# Titan_v1p1_180.net
KiCad netlist of a schematic drawn in EAGLE
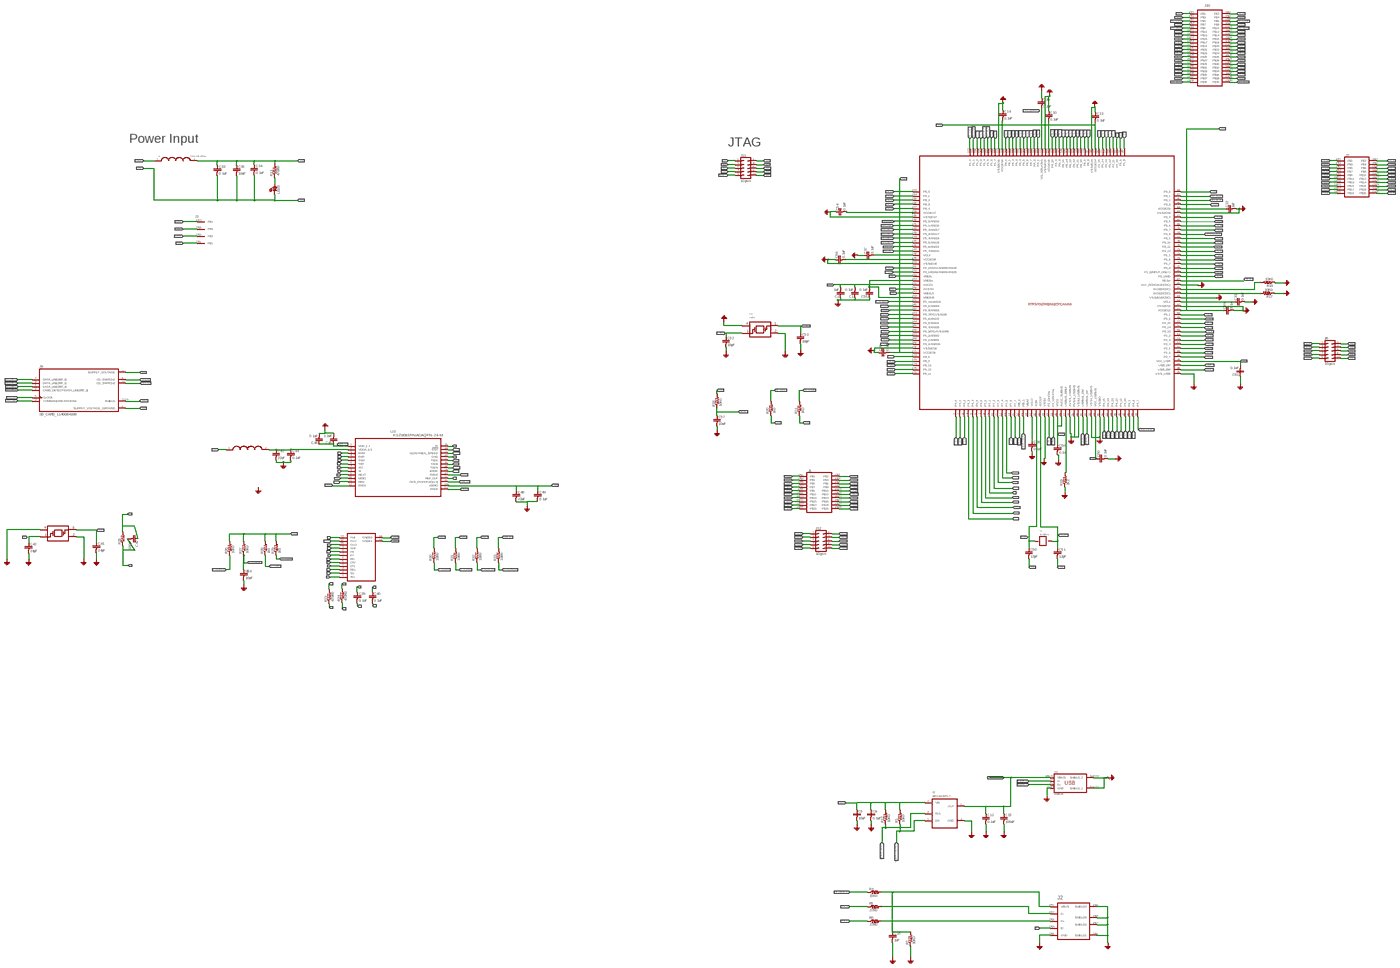
[diagram p0: schematic, sheet 1, overview]
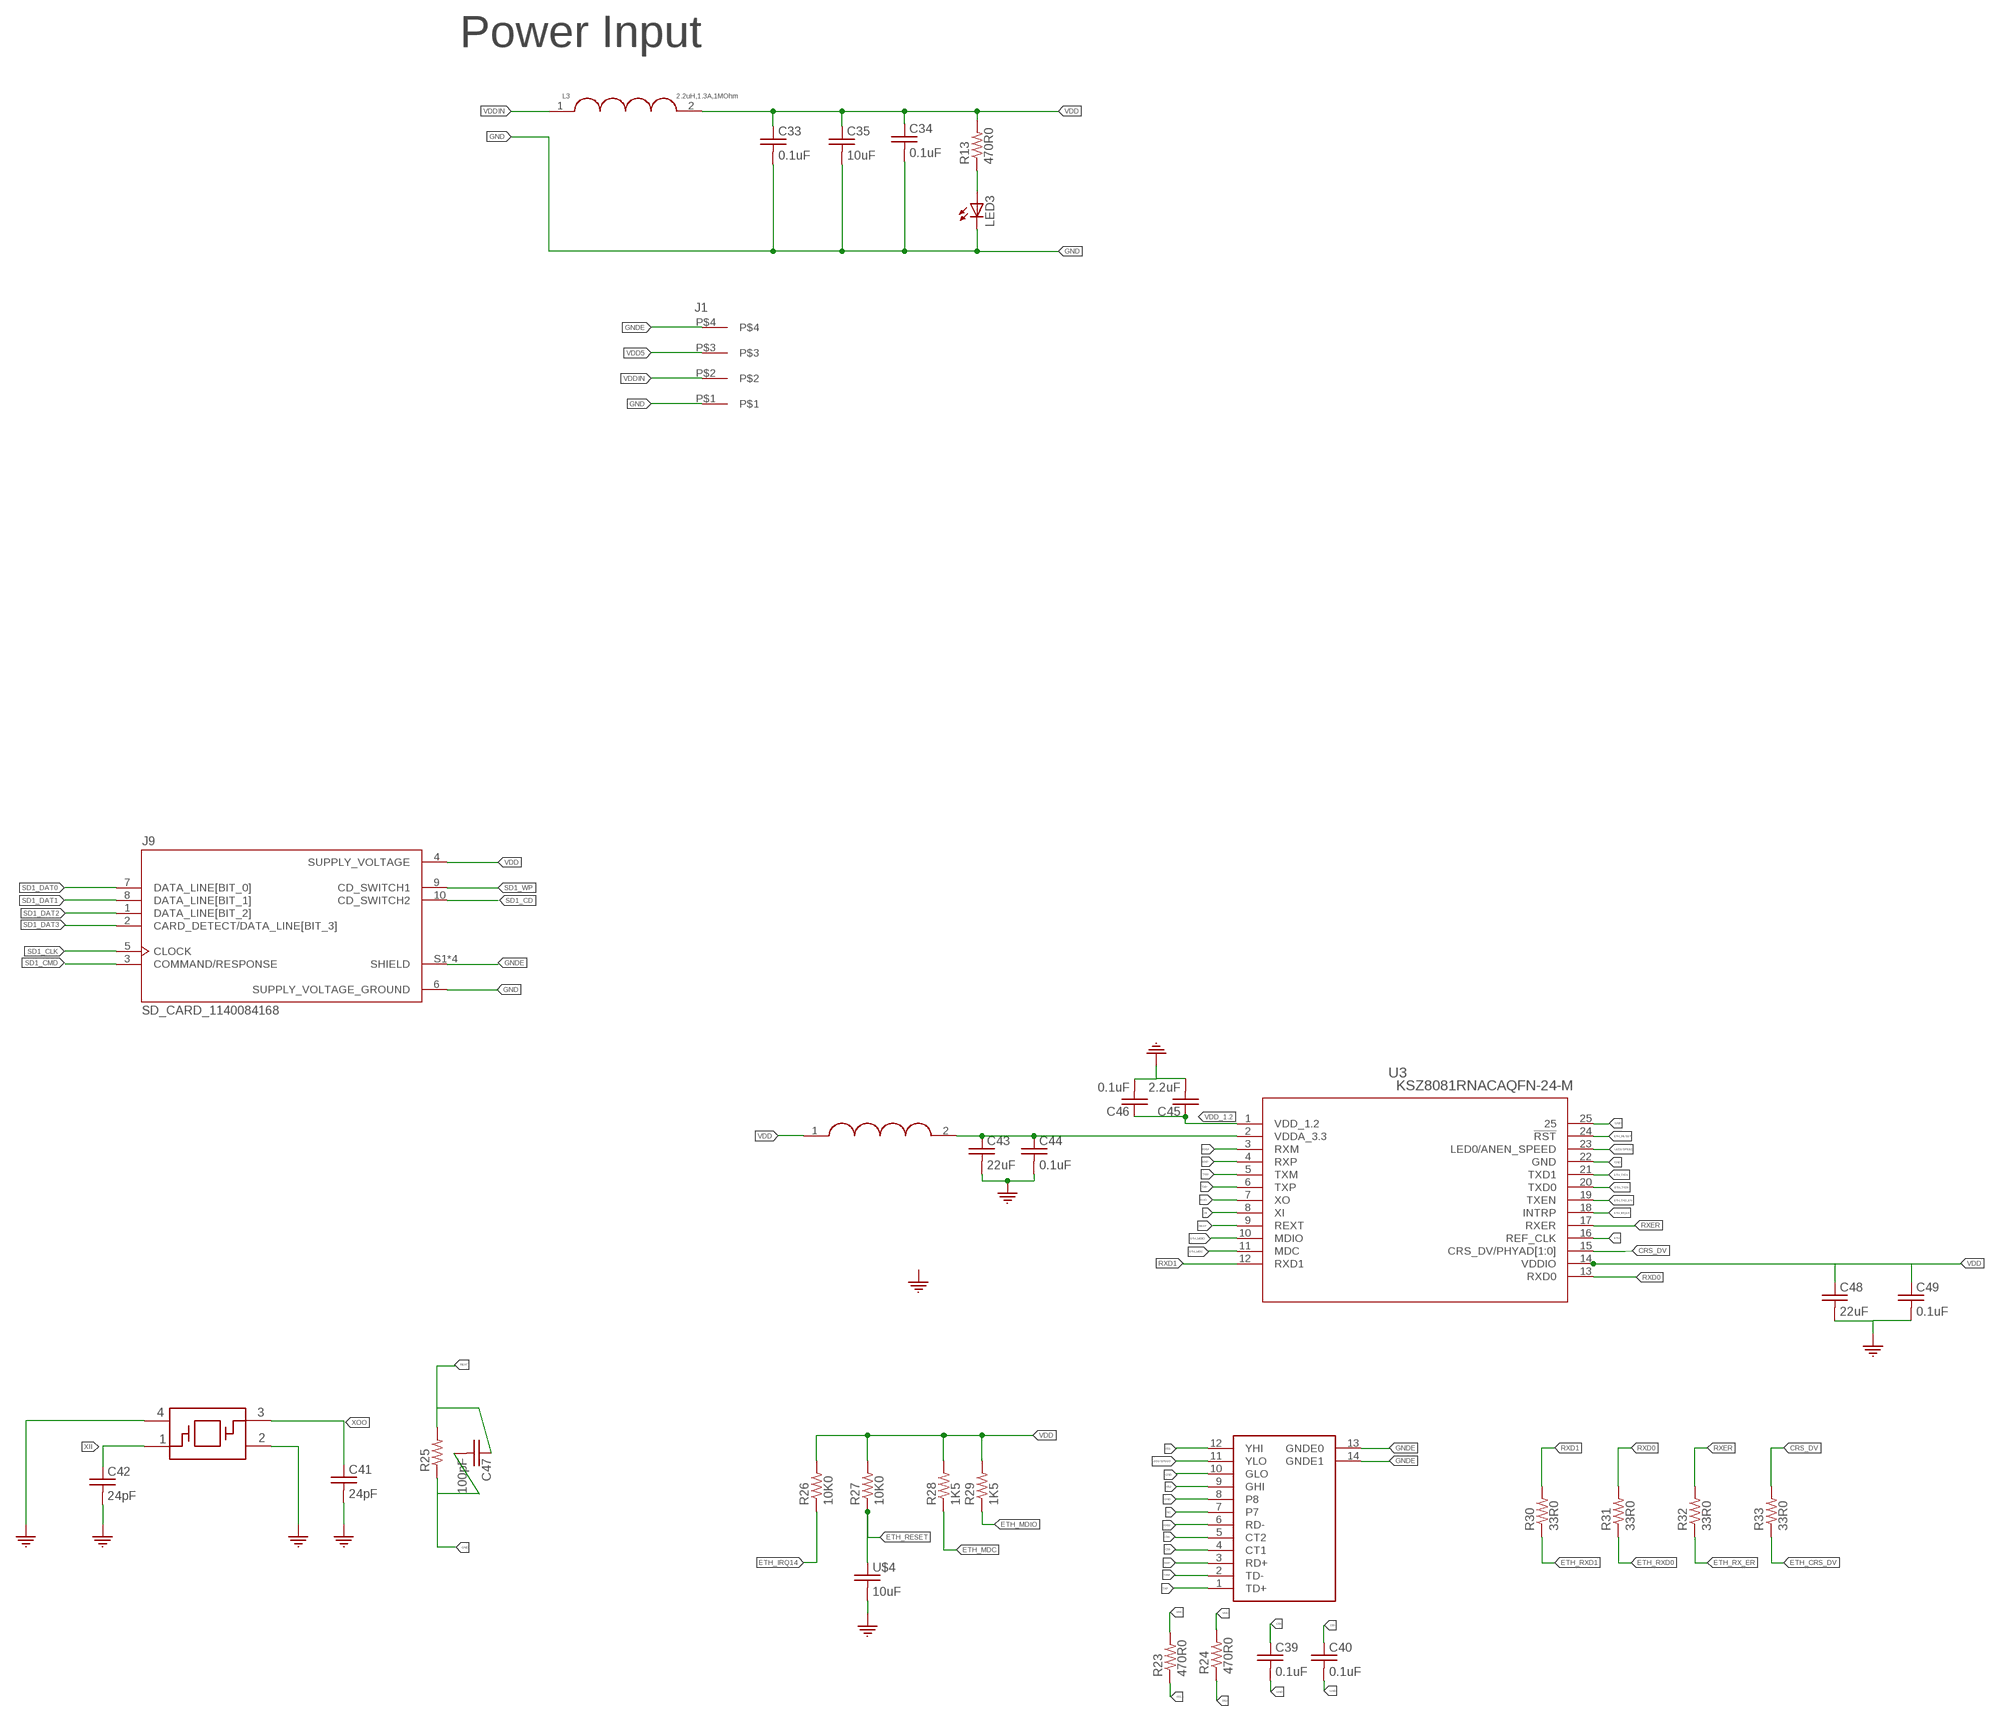
[diagram p1: schematic, sheet 1, part 1 of 4]
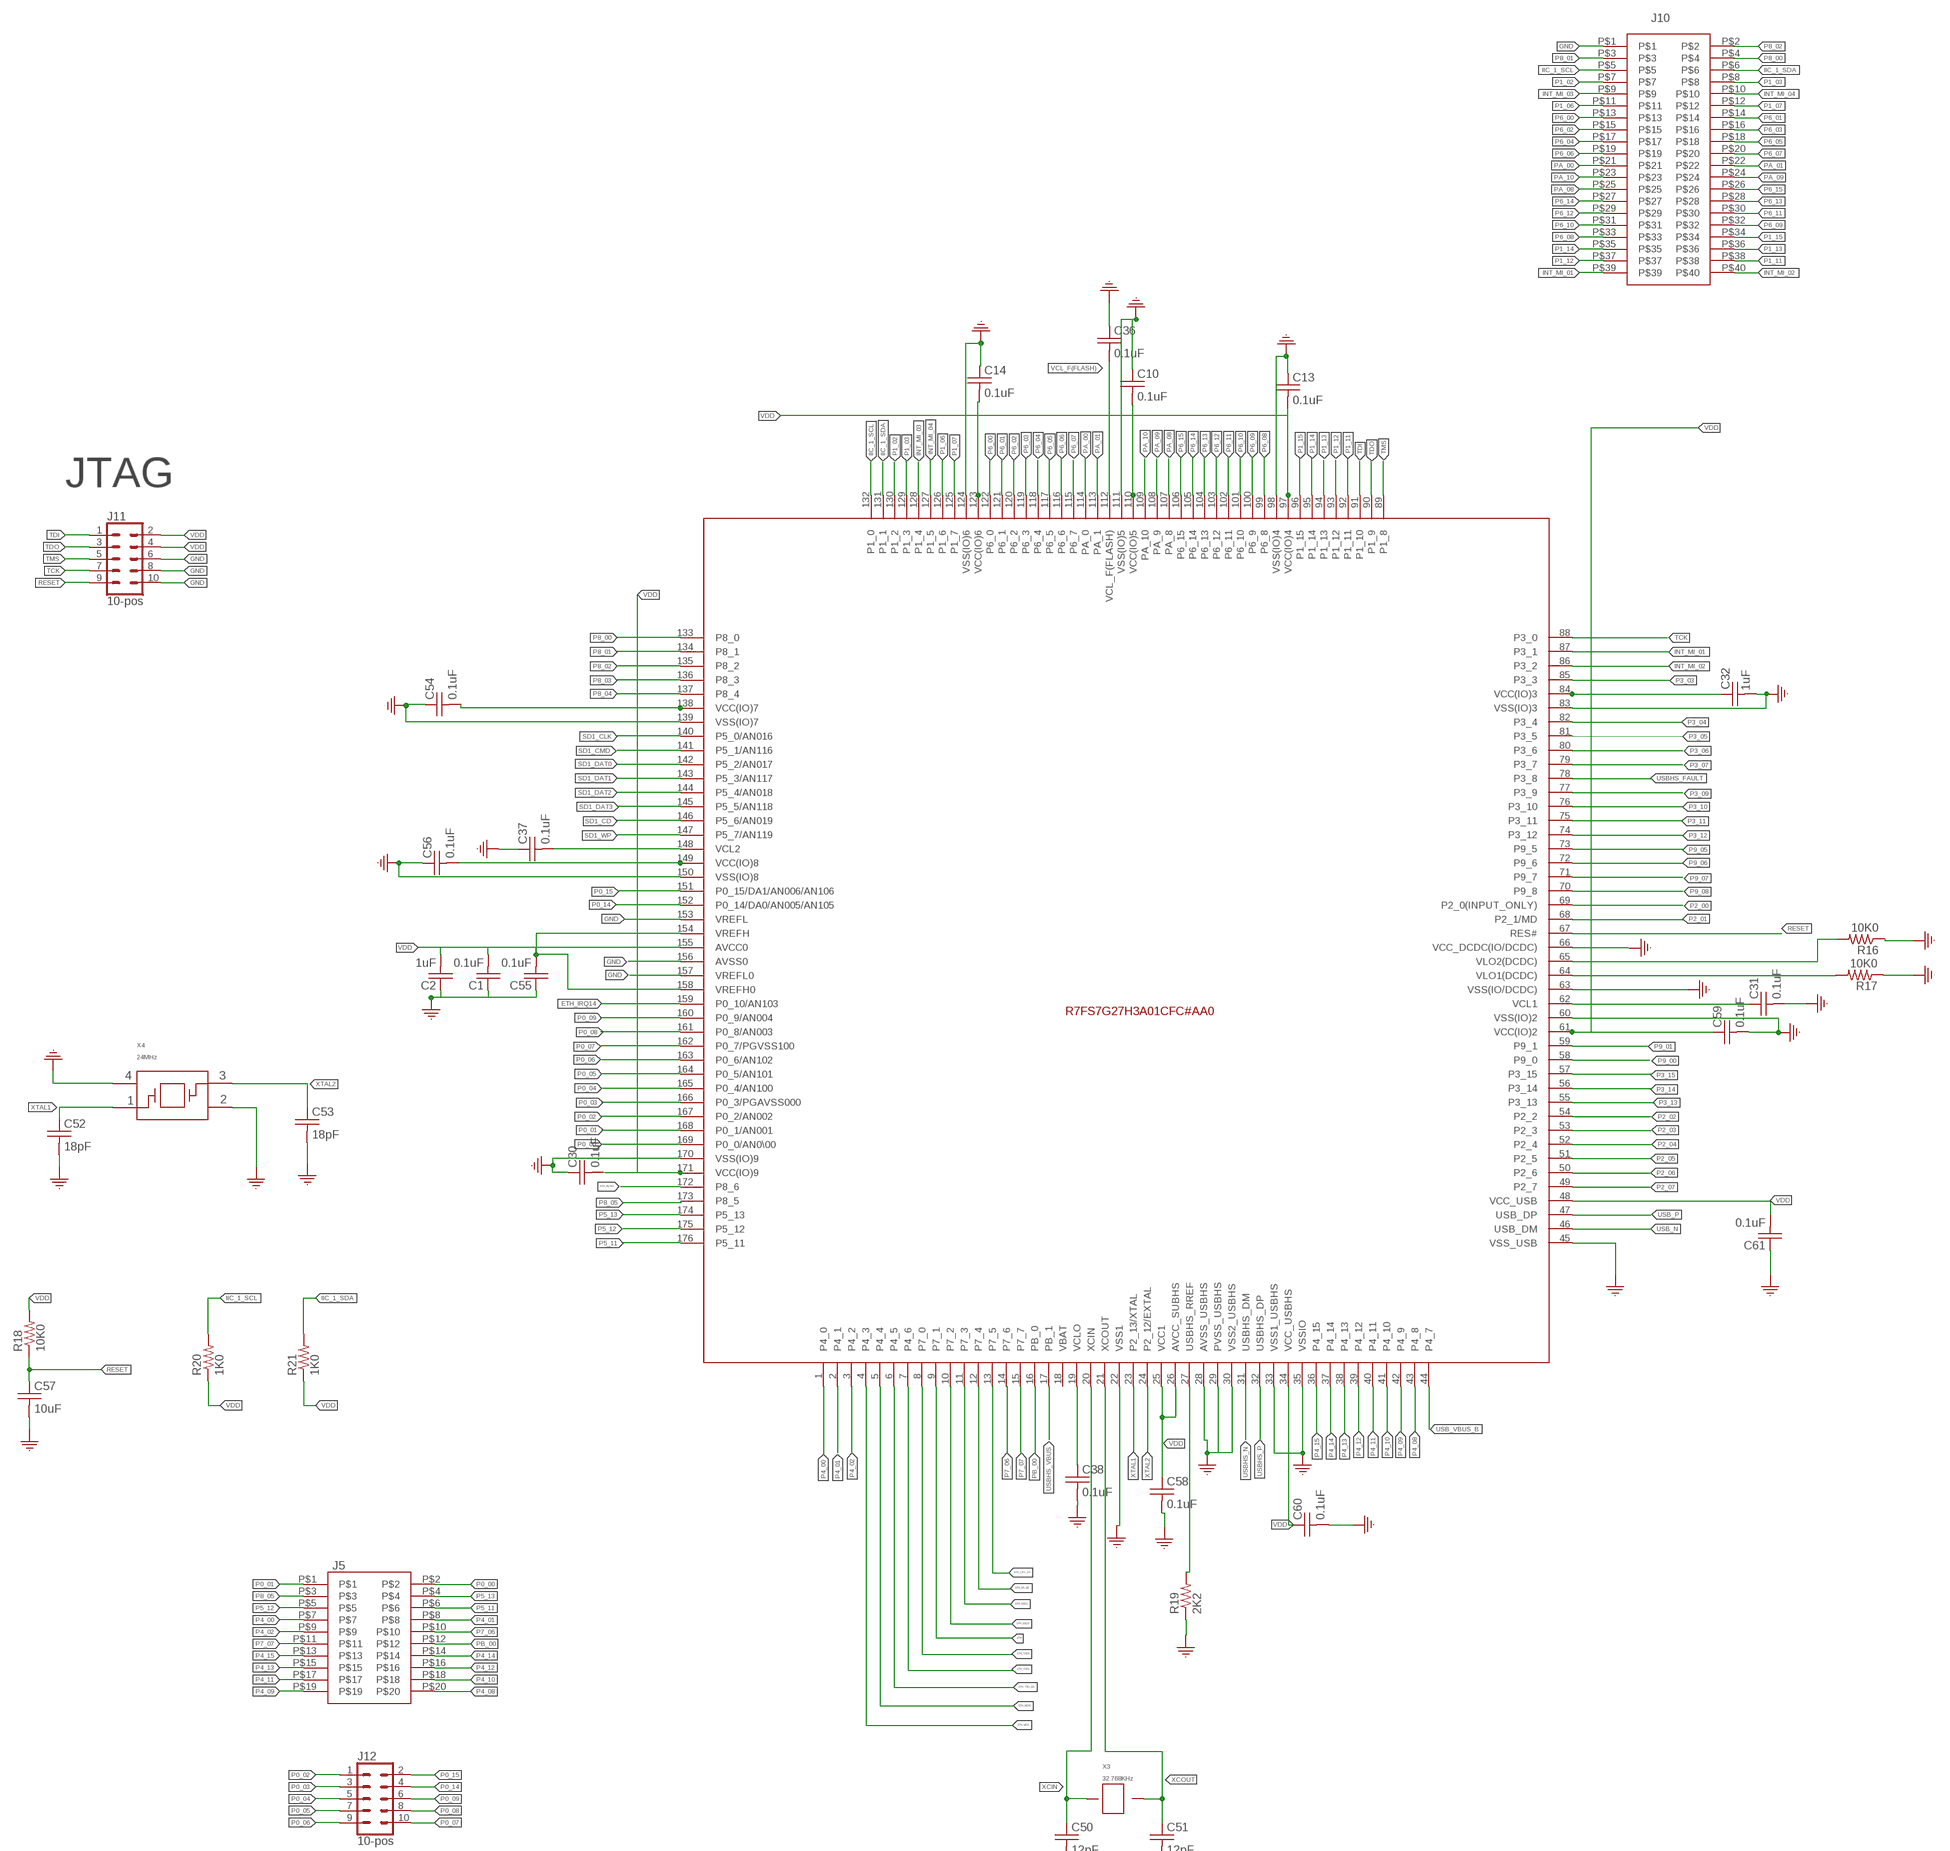
[diagram p2: schematic, sheet 1, part 2 of 4]
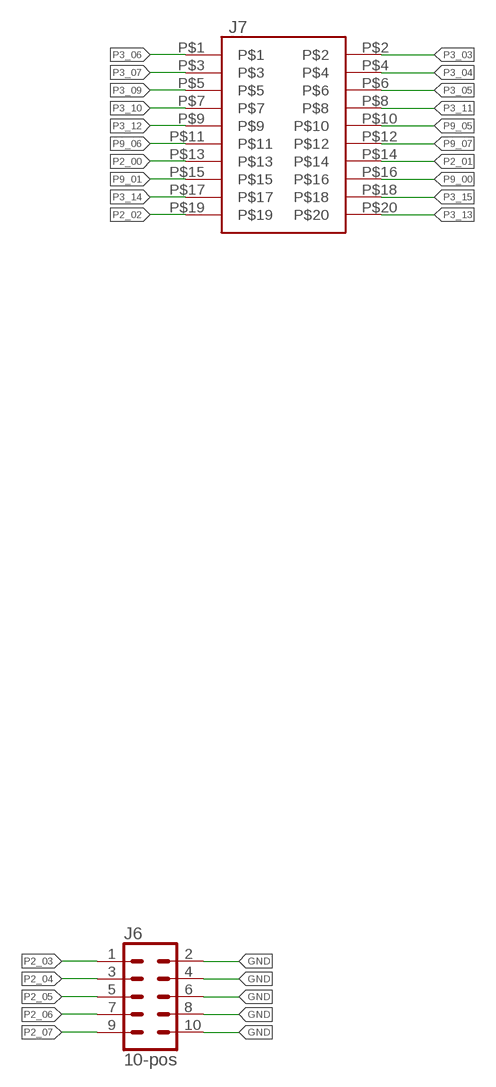
[diagram p3: schematic, sheet 1, part 3 of 4]
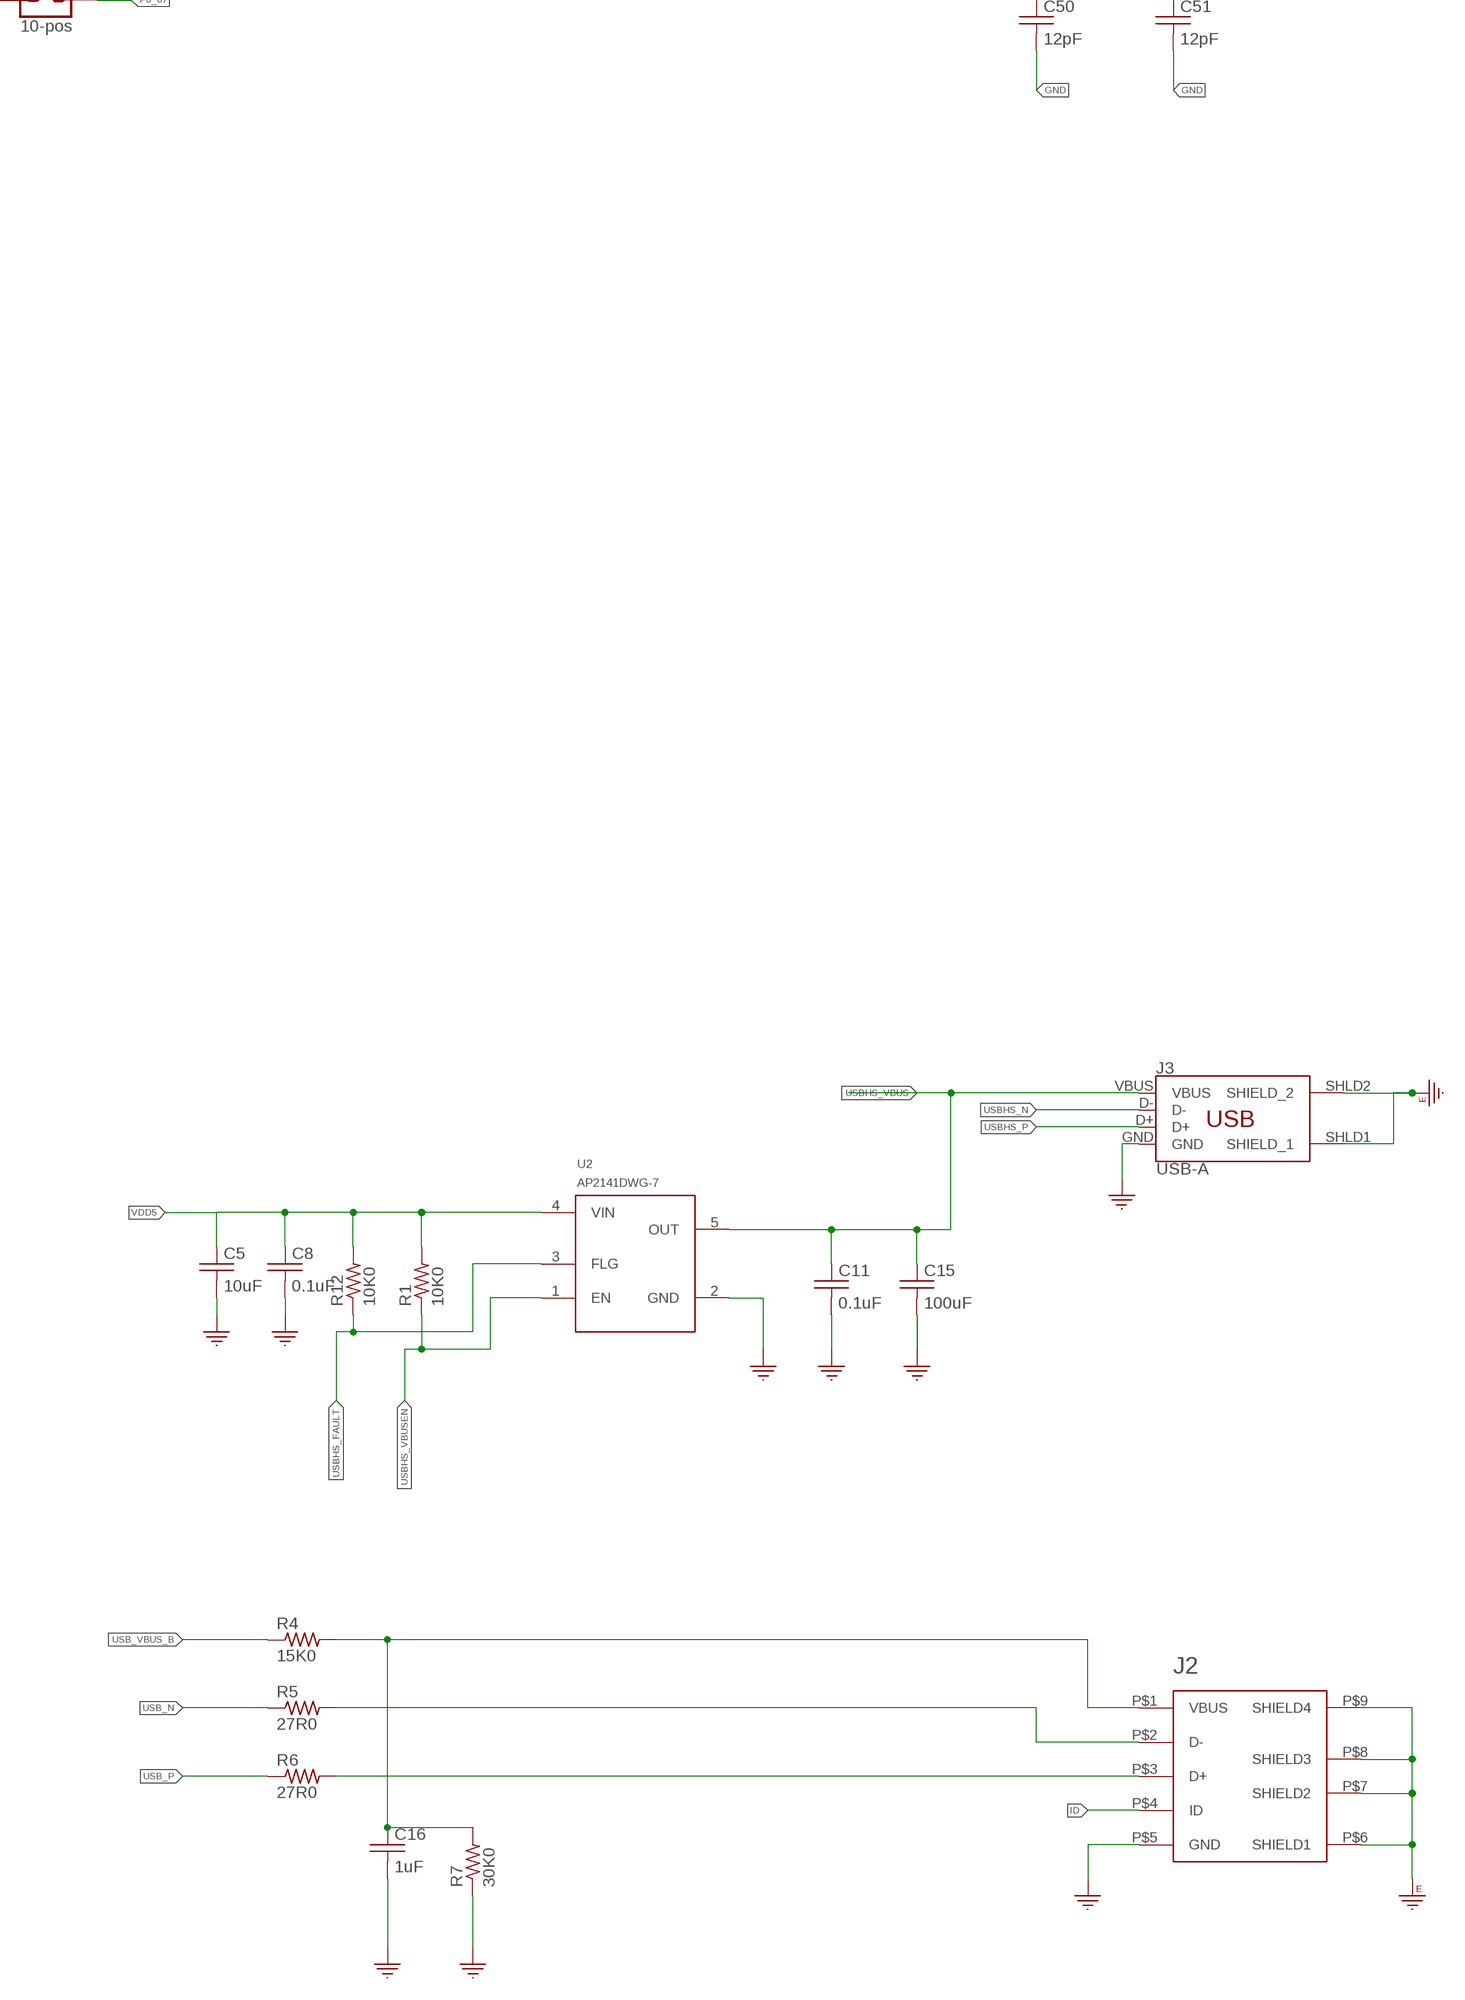
[diagram p4: schematic, sheet 1, part 4 of 4]

(export (version "E")
  (design (tool "Eeschema 10.0.6"))
  (components
    (comp (ref "C1")
      (value "0.1uF")
      (footprint "eagle-import:0402")
      (fields (field (name "PARTNO") "CL05F104ZO5NNNC"))
      (libsource (lib "eagle-import") (part "C_0402_0.1UF"))
    )
    (comp (ref "C2")
      (value "1uF")
      (footprint "eagle-import:0402")
      (fields (field (name "PARTNO") "CL05A105KO5NNNC"))
      (libsource (lib "eagle-import") (part "C_0402_1UF"))
    )
    (comp (ref "C5")
      (value "10uF")
      (footprint "eagle-import:0402")
      (fields (field (name "PARTNO") "CL05A106MP8NUB8"))
      (libsource (lib "eagle-import") (part "C_0402_10UF"))
    )
    (comp (ref "C8")
      (value "0.1uF")
      (footprint "eagle-import:0402")
      (fields (field (name "PARTNO") "CL05F104ZO5NNNC"))
      (libsource (lib "eagle-import") (part "C_0402_0.1UF"))
    )
    (comp (ref "C10")
      (value "0.1uF")
      (footprint "eagle-import:0402")
      (fields (field (name "PARTNO") "CL05F104ZO5NNNC"))
      (libsource (lib "eagle-import") (part "C_0402_0.1UF"))
    )
    (comp (ref "C11")
      (value "0.1uF")
      (footprint "eagle-import:0402")
      (fields (field (name "PARTNO") "CL05F104ZO5NNNC"))
      (libsource (lib "eagle-import") (part "C_0402_0.1UF"))
    )
    (comp (ref "C13")
      (value "0.1uF")
      (footprint "eagle-import:0402")
      (fields (field (name "PARTNO") "CL05F104ZO5NNNC"))
      (libsource (lib "eagle-import") (part "C_0402_0.1UF"))
    )
    (comp (ref "C14")
      (value "0.1uF")
      (footprint "eagle-import:0402")
      (fields (field (name "PARTNO") "CL05F104ZO5NNNC"))
      (libsource (lib "eagle-import") (part "C_0402_0.1UF"))
    )
    (comp (ref "C15")
      (value "100uF")
      (footprint "eagle-import:C1210")
      (fields (field (name "PARTNO") "TL8A0107M010D"))
      (libsource (lib "eagle-import") (part "C_1210"))
    )
    (comp (ref "C16")
      (value "1uF")
      (footprint "eagle-import:0402")
      (fields (field (name "PARTNO") "CL05A105KO5NNNC"))
      (libsource (lib "eagle-import") (part "C_0402_1UF"))
    )
    (comp (ref "C30")
      (value "0.1uF")
      (footprint "eagle-import:0402")
      (fields (field (name "PARTNO") "CL05F104ZO5NNNC"))
      (libsource (lib "eagle-import") (part "C_0402_0.1UF"))
    )
    (comp (ref "C31")
      (value "0.1uF")
      (footprint "eagle-import:0402")
      (fields (field (name "PARTNO") "CL05F104ZO5NNNC"))
      (libsource (lib "eagle-import") (part "C_0402_0.1UF"))
    )
    (comp (ref "C32")
      (value "1uF")
      (footprint "eagle-import:0402")
      (fields (field (name "PARTNO") "CL05A105KO5NNNC"))
      (libsource (lib "eagle-import") (part "C_0402_1UF"))
    )
    (comp (ref "C33")
      (value "0.1uF")
      (footprint "eagle-import:0402")
      (fields (field (name "PARTNO") "CL05F104ZO5NNNC"))
      (libsource (lib "eagle-import") (part "C_0402_0.1UF"))
    )
    (comp (ref "C34")
      (value "0.1uF")
      (footprint "eagle-import:0402")
      (fields (field (name "PARTNO") "CL05F104ZO5NNNC"))
      (libsource (lib "eagle-import") (part "C_0402_0.1UF"))
    )
    (comp (ref "C35")
      (value "10uF")
      (footprint "eagle-import:0402")
      (fields (field (name "PARTNO") "CL05A106MP8NUB8"))
      (libsource (lib "eagle-import") (part "C_0402_10UF"))
    )
    (comp (ref "C36")
      (value "0.1uF")
      (footprint "eagle-import:0402")
      (fields (field (name "PARTNO") "CL05F104ZO5NNNC"))
      (libsource (lib "eagle-import") (part "C_0402_0.1UF"))
    )
    (comp (ref "C37")
      (value "0.1uF")
      (footprint "eagle-import:0402")
      (fields (field (name "PARTNO") "CL05F104ZO5NNNC"))
      (libsource (lib "eagle-import") (part "C_0402_0.1UF"))
    )
    (comp (ref "C38")
      (value "0.1uF")
      (footprint "eagle-import:0402")
      (fields (field (name "PARTNO") "CL05F104ZO5NNNC"))
      (libsource (lib "eagle-import") (part "C_0402_0.1UF"))
    )
    (comp (ref "C39")
      (value "0.1uF")
      (footprint "eagle-import:0402")
      (fields (field (name "PARTNO") "CL05F104ZO5NNNC"))
      (libsource (lib "eagle-import") (part "C_0402_0.1UF"))
    )
    (comp (ref "C40")
      (value "0.1uF")
      (footprint "eagle-import:0402")
      (fields (field (name "PARTNO") "CL05F104ZO5NNNC"))
      (libsource (lib "eagle-import") (part "C_0402_0.1UF"))
    )
    (comp (ref "C41")
      (value "24pF")
      (footprint "eagle-import:0402")
      (fields (field (name "PARTNO") "CC0402GRNPO9BN240"))
      (libsource (lib "eagle-import") (part "C_0402_24PF"))
    )
    (comp (ref "C42")
      (value "24pF")
      (footprint "eagle-import:0402")
      (fields (field (name "PARTNO") "CC0402GRNPO9BN240"))
      (libsource (lib "eagle-import") (part "C_0402_24PF"))
    )
    (comp (ref "C43")
      (value "22uF")
      (footprint "eagle-import:0402")
      (fields (field (name "PARTNO") "CL05A226MQ5N6J8"))
      (libsource (lib "eagle-import") (part "C_0402_22UF"))
    )
    (comp (ref "C44")
      (value "0.1uF")
      (footprint "eagle-import:0402")
      (fields (field (name "PARTNO") "CL05F104ZO5NNNC"))
      (libsource (lib "eagle-import") (part "C_0402_0.1UF"))
    )
    (comp (ref "C45")
      (value "2.2uF")
      (footprint "eagle-import:0402")
      (fields (field (name "PARTNO") "GRM155C81C225ME15D"))
      (libsource (lib "eagle-import") (part "C_0402_2.2UF"))
    )
    (comp (ref "C46")
      (value "0.1uF")
      (footprint "eagle-import:0402")
      (fields (field (name "PARTNO") "CL05F104ZO5NNNC"))
      (libsource (lib "eagle-import") (part "C_0402_0.1UF"))
    )
    (comp (ref "C47")
      (value "100pF")
      (footprint "eagle-import:0402")
      (fields (field (name "PARTNO") "CL05C101JB5NNNC"))
      (libsource (lib "eagle-import") (part "C_0402_100PF"))
    )
    (comp (ref "C48")
      (value "22uF")
      (footprint "eagle-import:0402")
      (fields (field (name "PARTNO") "CL05A226MQ5N6J8"))
      (libsource (lib "eagle-import") (part "C_0402_22UF"))
    )
    (comp (ref "C49")
      (value "0.1uF")
      (footprint "eagle-import:0402")
      (fields (field (name "PARTNO") "CL05F104ZO5NNNC"))
      (libsource (lib "eagle-import") (part "C_0402_0.1UF"))
    )
    (comp (ref "C50")
      (value "12pF")
      (footprint "eagle-import:0402")
      (fields (field (name "PARTNO") "CL05C120JB5NNNC"))
      (libsource (lib "eagle-import") (part "C_0402_12PF"))
    )
    (comp (ref "C51")
      (value "12pF")
      (footprint "eagle-import:0402")
      (fields (field (name "PARTNO") "CL05C120JB5NNNC"))
      (libsource (lib "eagle-import") (part "C_0402_12PF"))
    )
    (comp (ref "C52")
      (value "18pF")
      (footprint "eagle-import:0402")
      (fields (field (name "PARTNO") "UMK105CG180JV-F"))
      (libsource (lib "eagle-import") (part "C_0402_18PF"))
    )
    (comp (ref "C53")
      (value "18pF")
      (footprint "eagle-import:0402")
      (fields (field (name "PARTNO") "UMK105CG180JV-F"))
      (libsource (lib "eagle-import") (part "C_0402_18PF"))
    )
    (comp (ref "C54")
      (value "0.1uF")
      (footprint "eagle-import:0402")
      (fields (field (name "PARTNO") "CL05F104ZO5NNNC"))
      (libsource (lib "eagle-import") (part "C_0402_0.1UF"))
    )
    (comp (ref "C55")
      (value "0.1uF")
      (footprint "eagle-import:0402")
      (fields (field (name "PARTNO") "CL05F104ZO5NNNC"))
      (libsource (lib "eagle-import") (part "C_0402_0.1UF"))
    )
    (comp (ref "C56")
      (value "0.1uF")
      (footprint "eagle-import:0402")
      (fields (field (name "PARTNO") "CL05F104ZO5NNNC"))
      (libsource (lib "eagle-import") (part "C_0402_0.1UF"))
    )
    (comp (ref "C57")
      (value "10uF")
      (footprint "eagle-import:0402")
      (fields (field (name "PARTNO") "CL05A106MP8NUB8"))
      (libsource (lib "eagle-import") (part "C_0402_10UF"))
    )
    (comp (ref "C58")
      (value "0.1uF")
      (footprint "eagle-import:0402")
      (fields (field (name "PARTNO") "CL05F104ZO5NNNC"))
      (libsource (lib "eagle-import") (part "C_0402_0.1UF"))
    )
    (comp (ref "C59")
      (value "0.1uF")
      (footprint "eagle-import:0402")
      (fields (field (name "PARTNO") "CL05F104ZO5NNNC"))
      (libsource (lib "eagle-import") (part "C_0402_0.1UF"))
    )
    (comp (ref "C60")
      (value "0.1uF")
      (footprint "eagle-import:0402")
      (fields (field (name "PARTNO") "CL05F104ZO5NNNC"))
      (libsource (lib "eagle-import") (part "C_0402_0.1UF"))
    )
    (comp (ref "C61")
      (value "0.1uF")
      (footprint "eagle-import:0402")
      (fields (field (name "PARTNO") "CL05F104ZO5NNNC"))
      (libsource (lib "eagle-import") (part "C_0402_0.1UF"))
    )
    (comp (ref "FB2/2")
      (value "120Ohm")
      (footprint "eagle-import:0603")
      (fields (field (name "PARTNO") "BLM18PG121SN1D"))
      (libsource (lib "eagle-import") (part "FB_0603_120_OHM0603"))
    )
    (comp (ref "J1")
      (value "4-pos")
      (footprint "eagle-import:1X4_3.81MM_PITCH")
      (fields (field (name "PARTNO") "691322310004"))
      (libsource (lib "eagle-import") (part "3.81MM_1_X_4_RT_ANGLE_PLUG_HEADER"))
    )
    (comp (ref "J2")
      (value "USB-B-Micro")
      (footprint "eagle-import:USB_MICRO-B")
      (fields (field (name "PARTNO") "10118192-0002LF"))
      (libsource (lib "eagle-import") (part "USB_MICRO-B"))
    )
    (comp (ref "J3")
      (value "USB-A")
      (footprint "eagle-import:USB_A_SMT")
      (fields (field (name "PARTNO") "87583-3010RPALF"))
      (libsource (lib "eagle-import") (part "USB_A"))
    )
    (comp (ref "J4")
      (value "RJ45")
      (footprint "eagle-import:RJ45_TH_ELEC")
      (fields (field (name "PARTNO") "13F-64GYD2PL2NL"))
      (libsource (lib "eagle-import") (part "RJ45_WITH_ELEC"))
    )
    (comp (ref "J5")
      (value "20-pos")
      (footprint "eagle-import:2_X_10_.1_INCH")
      (fields (field (name "PARTNO") "67996-420HLF"))
      (libsource (lib "eagle-import") (part "2_X_10_HEADER_GENERIC"))
    )
    (comp (ref "J6")
      (value "10-pos")
      (footprint "eagle-import:2X5")
      (fields (field (name "PARTNO") "PH2RA-10-UA"))
      (libsource (lib "eagle-import") (part "CONN_05X2_RAPTH"))
    )
    (comp (ref "J7")
      (value "20-pos")
      (footprint "eagle-import:2_X_10_.1_INCH")
      (fields (field (name "PARTNO") "67996-420HLF"))
      (libsource (lib "eagle-import") (part "2_X_10_HEADER_GENERIC"))
    )
    (comp (ref "J9")
      (value "SD_CARD_1140084168")
      (footprint "eagle-import:SD_CARD")
      (fields (field (name "MF") "Amphenol ICC") (field (name "PARTNO") "114-00841-68"))
      (libsource (lib "eagle-import") (part "SD_CARD_1140084168"))
    )
    (comp (ref "J10")
      (value "40-pos")
      (footprint "eagle-import:HEADER_2_X_20_.1_INCH")
      (fields (field (name "PARTNO") "61304021021"))
      (libsource (lib "eagle-import") (part "HEADER_2_X_20_GENERIC"))
    )
    (comp (ref "J11")
      (value "10-pos")
      (footprint "eagle-import:2X5")
      (fields (field (name "PARTNO") "PH2RA-10-UA"))
      (libsource (lib "eagle-import") (part "CONN_05X2_RAPTH"))
    )
    (comp (ref "J12")
      (value "10-pos")
      (footprint "eagle-import:2X5")
      (fields (field (name "PARTNO") "PH2RA-10-UA"))
      (libsource (lib "eagle-import") (part "CONN_05X2_RAPTH"))
    )
    (comp (ref "L3")
      (value "2.2uH,1.3A,1MOhm")
      (footprint "eagle-import:1008")
      (fields (field (name "PARTNO") "LQM2HPN2R2MG0L"))
      (libsource (lib "eagle-import") (part "INDUCTOR_1008_2.2_MH_1.3A"))
    )
    (comp (ref "LED3")
      (value "Green")
      (footprint "eagle-import:0805")
      (fields (field (name "PARTNO") "LG R971-KN-1"))
      (libsource (lib "eagle-import") (part "LED_0805_GREEN"))
    )
    (comp (ref "R1")
      (value "10K0")
      (footprint "eagle-import:0402")
      (fields (field (name "PARTNO") "RMCF0402JT10K0"))
      (libsource (lib "eagle-import") (part "R_0402_10K0"))
    )
    (comp (ref "R4")
      (value "15K0")
      (footprint "eagle-import:0402")
      (fields (field (name "PARTNO") "RMCF0402JT15K0"))
      (libsource (lib "eagle-import") (part "R_0402_15K0"))
    )
    (comp (ref "R5")
      (value "27R0")
      (footprint "eagle-import:0402")
      (fields (field (name "PARTNO") "RMCF0402JT27R0"))
      (libsource (lib "eagle-import") (part "R_0402_27R0"))
    )
    (comp (ref "R6")
      (value "27R0")
      (footprint "eagle-import:0402")
      (fields (field (name "PARTNO") "RMCF0402JT27R0"))
      (libsource (lib "eagle-import") (part "R_0402_27R0"))
    )
    (comp (ref "R7")
      (value "30K0")
      (footprint "eagle-import:0402")
      (fields (field (name "PARTNO") "RC0402JR-0730KL"))
      (libsource (lib "eagle-import") (part "R_0402_30K0"))
    )
    (comp (ref "R12")
      (value "10K0")
      (footprint "eagle-import:0402")
      (fields (field (name "PARTNO") "RMCF0402JT10K0"))
      (libsource (lib "eagle-import") (part "R_0402_10K0"))
    )
    (comp (ref "R13")
      (value "470R0")
      (footprint "eagle-import:0402")
      (fields (field (name "PARTNO") "RMCF0402JT470R"))
      (libsource (lib "eagle-import") (part "R_0402_470R0"))
    )
    (comp (ref "R16")
      (value "10K0")
      (footprint "eagle-import:0402")
      (fields (field (name "PARTNO") "RMCF0402JT10K0"))
      (libsource (lib "eagle-import") (part "R_0402_10K0"))
    )
    (comp (ref "R17")
      (value "10K0")
      (footprint "eagle-import:0402")
      (fields (field (name "PARTNO") "RMCF0402JT10K0"))
      (libsource (lib "eagle-import") (part "R_0402_10K0"))
    )
    (comp (ref "R18")
      (value "10K0")
      (footprint "eagle-import:0402")
      (fields (field (name "PARTNO") "RMCF0402JT10K0"))
      (libsource (lib "eagle-import") (part "R_0402_10K0"))
    )
    (comp (ref "R19")
      (value "2K2")
      (footprint "eagle-import:0402")
      (fields (field (name "PARTNO") "RMCF0402JT2K20"))
      (libsource (lib "eagle-import") (part "R_0402_2K2"))
    )
    (comp (ref "R20")
      (value "1K0")
      (footprint "eagle-import:0402")
      (fields (field (name "PARTNO") "CRG0402J1K0"))
      (libsource (lib "eagle-import") (part "R_0402_1K0"))
    )
    (comp (ref "R21")
      (value "1K0")
      (footprint "eagle-import:0402")
      (fields (field (name "PARTNO") "CRG0402J1K0"))
      (libsource (lib "eagle-import") (part "R_0402_1K0"))
    )
    (comp (ref "R23")
      (value "470R0")
      (footprint "eagle-import:0402")
      (fields (field (name "PARTNO") "RMCF0402JT470R"))
      (libsource (lib "eagle-import") (part "R_0402_470R0"))
    )
    (comp (ref "R24")
      (value "470R0")
      (footprint "eagle-import:0402")
      (fields (field (name "PARTNO") "RMCF0402JT470R"))
      (libsource (lib "eagle-import") (part "R_0402_470R0"))
    )
    (comp (ref "R25")
      (value "6K49")
      (footprint "eagle-import:0402")
      (fields (field (name "PARTNO") "RMCF0402FT6K49"))
      (libsource (lib "eagle-import") (part "R_0402_6K49"))
    )
    (comp (ref "R26")
      (value "10K0")
      (footprint "eagle-import:0402")
      (fields (field (name "PARTNO") "RMCF0402JT10K0"))
      (libsource (lib "eagle-import") (part "R_0402_10K0"))
    )
    (comp (ref "R27")
      (value "10K0")
      (footprint "eagle-import:0402")
      (fields (field (name "PARTNO") "RMCF0402JT10K0"))
      (libsource (lib "eagle-import") (part "R_0402_10K0"))
    )
    (comp (ref "R28")
      (value "1K5")
      (footprint "eagle-import:0402")
      (fields (field (name "PARTNO") "RMCF0402JT1K50"))
      (libsource (lib "eagle-import") (part "R_0402_1K5"))
    )
    (comp (ref "R29")
      (value "1K5")
      (footprint "eagle-import:0402")
      (fields (field (name "PARTNO") "RMCF0402JT1K50"))
      (libsource (lib "eagle-import") (part "R_0402_1K5"))
    )
    (comp (ref "R30")
      (value "33R0")
      (footprint "eagle-import:0402")
      (fields (field (name "PARTNO") "RMCF0402JT33R0"))
      (libsource (lib "eagle-import") (part "R_0402_33R0"))
    )
    (comp (ref "R31")
      (value "33R0")
      (footprint "eagle-import:0402")
      (fields (field (name "PARTNO") "RMCF0402JT33R0"))
      (libsource (lib "eagle-import") (part "R_0402_33R0"))
    )
    (comp (ref "R32")
      (value "33R0")
      (footprint "eagle-import:0402")
      (fields (field (name "PARTNO") "RMCF0402JT33R0"))
      (libsource (lib "eagle-import") (part "R_0402_33R0"))
    )
    (comp (ref "R33")
      (value "33R0")
      (footprint "eagle-import:0402")
      (fields (field (name "PARTNO") "RMCF0402JT33R0"))
      (libsource (lib "eagle-import") (part "R_0402_33R0"))
    )
    (comp (ref "U$4")
      (value "10uF")
      (footprint "eagle-import:0402")
      (fields (field (name "PARTNO") "CL05A106MP8NUB8"))
      (libsource (lib "eagle-import") (part "C_0402_10UF"))
    )
    (comp (ref "U2")
      (value "AP2151DWG-7")
      (footprint "eagle-import:SOT-23-5")
      (fields (field (name "PARTNO") "AP2151WG-7"))
      (libsource (lib "eagle-import") (part "AP2151DWG-7"))
    )
    (comp (ref "U3")
      (value "KSZ8081RNACAQFN-24-M")
      (footprint "eagle-import:QFN-24-M")
      (fields (field (name "PARTNO") "KSZ8081RNACA"))
      (libsource (lib "eagle-import") (part "KSZ8081RNACAQFN-24-M"))
    )
    (comp (ref "U4")
      (value "S7G2LQFP176")
      (footprint "eagle-import:LQFP176_24X24")
      (fields (field (name "PARTNO") "R7FS7G27H3A01CFC#AA0"))
      (libsource (lib "eagle-import") (part "S7G2_X_176"))
    )
    (comp (ref "U5")
      (value "25MHz")
      (footprint "eagle-import:SMD_3225")
      (fields (field (name "PARTNO") "FA-238 25.0000MB-B3"))
      (libsource (lib "eagle-import") (part "XTAL_25_MHZ"))
    )
    (comp (ref "X3")
      (value "32.768KHz")
      (footprint "eagle-import:SMD_X_2_PADS")
      (fields (field (name "PARTNO") "ABS07-32.768KHZ-T"))
      (libsource (lib "eagle-import") (part "XTAL_32.768KHZ"))
    )
    (comp (ref "X4")
      (value "24MHz")
      (footprint "eagle-import:SMD_3225")
      (fields (field (name "PARTNO") "FA-238 24.0000MB-C3 "))
      (libsource (lib "eagle-import") (part "XTAL_24_MHZ"))
    )
  )
  (nets
    (net (code "1") (name "C58") (class "Default")
      (node (ref "C39") (pin "P$1") (pinfunction "1_P$1") (pintype "passive"))
      (node (ref "J4") (pin "4") (pinfunction "CT1_4") (pintype "bidirectional"))
    )
    (net (code "2") (name "C60") (class "Default")
      (node (ref "C40") (pin "P$1") (pinfunction "1_P$1") (pintype "passive"))
      (node (ref "J4") (pin "5") (pinfunction "CT2_5") (pintype "bidirectional"))
    )
    (net (code "3") (name "CRS_DV") (class "Default")
      (node (ref "R33") (pin "P$2") (pinfunction "2_P$2") (pintype "passive"))
      (node (ref "U3") (pin "15") (pinfunction "CRS_DV/PHYAD[1:0]_15") (pintype "bidirectional"))
    )
    (net (code "4") (name "ETH") (class "Default")
      (node (ref "U3") (pin "16") (pinfunction "REF_CLK_16") (pintype "bidirectional"))
      (node (ref "U4") (pin "9") (pinfunction "P7_1_9") (pintype "bidirectional"))
    )
    (net (code "5") (name "ETH_CRS_DV") (class "Default")
      (node (ref "R33") (pin "P$1") (pinfunction "1_P$1") (pintype "passive"))
      (node (ref "U4") (pin "13") (pinfunction "P7_5_13") (pintype "bidirectional"))
    )
    (net (code "6") (name "ETH_IRQ14") (class "Default")
      (node (ref "R26") (pin "P$1") (pinfunction "1_P$1") (pintype "passive"))
      (node (ref "U3") (pin "18") (pinfunction "INTRP_18") (pintype "bidirectional"))
      (node (ref "U4") (pin "159") (pinfunction "P0_10/AN103_159") (pintype "bidirectional"))
    )
    (net (code "7") (name "ETH_MDC") (class "Default")
      (node (ref "R28") (pin "P$1") (pinfunction "1_P$1") (pintype "passive"))
      (node (ref "U3") (pin "11") (pinfunction "MDC_11") (pintype "input"))
      (node (ref "U4") (pin "4") (pinfunction "P4_3_4") (pintype "bidirectional"))
    )
    (net (code "8") (name "ETH_MDIO") (class "Default")
      (node (ref "R29") (pin "P$1") (pinfunction "1_P$1") (pintype "passive"))
      (node (ref "U3") (pin "10") (pinfunction "MDIO_10") (pintype "bidirectional"))
      (node (ref "U4") (pin "5") (pinfunction "P4_4_5") (pintype "bidirectional"))
    )
    (net (code "9") (name "ETH_RESET") (class "Default")
      (node (ref "R27") (pin "P$1") (pinfunction "1_P$1") (pintype "passive"))
      (node (ref "U$4") (pin "P$1") (pinfunction "1_P$1") (pintype "passive"))
      (node (ref "U3") (pin "24") (pinfunction "~{RST}_24") (pintype "input"))
      (node (ref "U4") (pin "172") (pinfunction "P8_6_172") (pintype "bidirectional"))
    )
    (net (code "10") (name "ETH_RXD0") (class "Default")
      (node (ref "R31") (pin "P$1") (pinfunction "1_P$1") (pintype "passive"))
      (node (ref "U4") (pin "10") (pinfunction "P7_2_10") (pintype "bidirectional"))
    )
    (net (code "11") (name "ETH_RXD1") (class "Default")
      (node (ref "R30") (pin "P$1") (pinfunction "1_P$1") (pintype "passive"))
      (node (ref "U4") (pin "11") (pinfunction "P7_3_11") (pintype "bidirectional"))
    )
    (net (code "12") (name "ETH_RX_ER") (class "Default")
      (node (ref "R32") (pin "P$1") (pinfunction "1_P$1") (pintype "passive"))
      (node (ref "U4") (pin "12") (pinfunction "P7_4_12") (pintype "bidirectional"))
    )
    (net (code "13") (name "ETH_TXD0") (class "Default")
      (node (ref "U3") (pin "20") (pinfunction "TXD0_20") (pintype "input"))
      (node (ref "U4") (pin "8") (pinfunction "P7_0_8") (pintype "bidirectional"))
    )
    (net (code "14") (name "ETH_TXD1") (class "Default")
      (node (ref "U3") (pin "21") (pinfunction "TXD1_21") (pintype "bidirectional"))
      (node (ref "U4") (pin "7") (pinfunction "P4_6_7") (pintype "bidirectional"))
    )
    (net (code "15") (name "ETH_TXD_EN") (class "Default")
      (node (ref "U3") (pin "19") (pinfunction "TXEN_19") (pintype "input"))
      (node (ref "U4") (pin "6") (pinfunction "P4_5_6") (pintype "bidirectional"))
    )
    (net (code "16") (name "GND") (class "Default")
      (node (ref "C1") (pin "P$1") (pinfunction "1_P$1") (pintype "passive"))
      (node (ref "C10") (pin "P$1") (pinfunction "1_P$1") (pintype "passive"))
      (node (ref "C11") (pin "P$2") (pinfunction "2_P$2") (pintype "passive"))
      (node (ref "C13") (pin "P$1") (pinfunction "1_P$1") (pintype "passive"))
      (node (ref "C14") (pin "P$1") (pinfunction "1_P$1") (pintype "passive"))
      (node (ref "C15") (pin "2") (pinfunction "2_2") (pintype "passive"))
      (node (ref "C16") (pin "P$2") (pinfunction "2_P$2") (pintype "passive"))
      (node (ref "C2") (pin "P$1") (pinfunction "1_P$1") (pintype "passive"))
      (node (ref "C30") (pin "P$1") (pinfunction "1_P$1") (pintype "passive"))
      (node (ref "C31") (pin "P$2") (pinfunction "2_P$2") (pintype "passive"))
      (node (ref "C32") (pin "P$2") (pinfunction "2_P$2") (pintype "passive"))
      (node (ref "C33") (pin "P$2") (pinfunction "2_P$2") (pintype "passive"))
      (node (ref "C34") (pin "P$2") (pinfunction "2_P$2") (pintype "passive"))
      (node (ref "C35") (pin "P$2") (pinfunction "2_P$2") (pintype "passive"))
      (node (ref "C36") (pin "P$1") (pinfunction "1_P$1") (pintype "passive"))
      (node (ref "C37") (pin "P$1") (pinfunction "1_P$1") (pintype "passive"))
      (node (ref "C38") (pin "P$2") (pinfunction "2_P$2") (pintype "passive"))
      (node (ref "C39") (pin "P$2") (pinfunction "2_P$2") (pintype "passive"))
      (node (ref "C40") (pin "P$2") (pinfunction "2_P$2") (pintype "passive"))
      (node (ref "C41") (pin "P$2") (pinfunction "2_P$2") (pintype "passive"))
      (node (ref "C42") (pin "P$2") (pinfunction "2_P$2") (pintype "passive"))
      (node (ref "C43") (pin "P$2") (pinfunction "2_P$2") (pintype "passive"))
      (node (ref "C44") (pin "P$2") (pinfunction "2_P$2") (pintype "passive"))
      (node (ref "C45") (pin "P$2") (pinfunction "2_P$2") (pintype "passive"))
      (node (ref "C46") (pin "P$2") (pinfunction "2_P$2") (pintype "passive"))
      (node (ref "C47") (pin "P$2") (pinfunction "2_P$2") (pintype "passive"))
      (node (ref "C48") (pin "P$2") (pinfunction "2_P$2") (pintype "passive"))
      (node (ref "C49") (pin "P$2") (pinfunction "2_P$2") (pintype "passive"))
      (node (ref "C5") (pin "P$2") (pinfunction "2_P$2") (pintype "passive"))
      (node (ref "C50") (pin "P$2") (pinfunction "2_P$2") (pintype "passive"))
      (node (ref "C51") (pin "P$2") (pinfunction "2_P$2") (pintype "passive"))
      (node (ref "C52") (pin "P$2") (pinfunction "2_P$2") (pintype "passive"))
      (node (ref "C53") (pin "P$2") (pinfunction "2_P$2") (pintype "passive"))
      (node (ref "C54") (pin "P$1") (pinfunction "1_P$1") (pintype "passive"))
      (node (ref "C55") (pin "P$1") (pinfunction "1_P$1") (pintype "passive"))
      (node (ref "C56") (pin "P$1") (pinfunction "1_P$1") (pintype "passive"))
      (node (ref "C57") (pin "P$2") (pinfunction "2_P$2") (pintype "passive"))
      (node (ref "C58") (pin "P$2") (pinfunction "2_P$2") (pintype "passive"))
      (node (ref "C59") (pin "P$2") (pinfunction "2_P$2") (pintype "passive"))
      (node (ref "C60") (pin "P$2") (pinfunction "2_P$2") (pintype "passive"))
      (node (ref "C61") (pin "P$1") (pinfunction "1_P$1") (pintype "passive"))
      (node (ref "C8") (pin "P$2") (pinfunction "2_P$2") (pintype "passive"))
      (node (ref "J1") (pin "P$1") (pinfunction "P$1_P$1") (pintype "bidirectional"))
      (node (ref "J10") (pin "P$1") (pinfunction "P$1_P$1") (pintype "bidirectional"))
      (node (ref "J11") (pin "10") (pinfunction "10_10") (pintype "passive"))
      (node (ref "J11") (pin "6") (pinfunction "6_6") (pintype "passive"))
      (node (ref "J11") (pin "8") (pinfunction "8_8") (pintype "passive"))
      (node (ref "J2") (pin "P$5") (pinfunction "GND_P$5") (pintype "bidirectional"))
      (node (ref "J3") (pin "GND") (pinfunction "GND_GND") (pintype "power_in"))
      (node (ref "J4") (pin "10") (pinfunction "GLO_10") (pintype "bidirectional"))
      (node (ref "J4") (pin "8") (pinfunction "P8_8") (pintype "bidirectional"))
      (node (ref "J6") (pin "10") (pinfunction "10_10") (pintype "passive"))
      (node (ref "J6") (pin "2") (pinfunction "2_2") (pintype "passive"))
      (node (ref "J6") (pin "4") (pinfunction "4_4") (pintype "passive"))
      (node (ref "J6") (pin "6") (pinfunction "6_6") (pintype "passive"))
      (node (ref "J6") (pin "8") (pinfunction "8_8") (pintype "passive"))
      (node (ref "J9") (pin "6") (pinfunction "SUPPLY_VOLTAGE_GROUND_6") (pintype "power_in"))
      (node (ref "LED3") (pin "2") (pinfunction "C_2") (pintype "passive"))
      (node (ref "R16") (pin "P$1") (pinfunction "1_P$1") (pintype "passive"))
      (node (ref "R17") (pin "P$1") (pinfunction "1_P$1") (pintype "passive"))
      (node (ref "R19") (pin "P$1") (pinfunction "1_P$1") (pintype "passive"))
      (node (ref "R25") (pin "P$1") (pinfunction "1_P$1") (pintype "passive"))
      (node (ref "R7") (pin "P$1") (pinfunction "1_P$1") (pintype "passive"))
      (node (ref "U$4") (pin "P$2") (pinfunction "2_P$2") (pintype "passive"))
      (node (ref "U2") (pin "2") (pinfunction "GND_2") (pintype "input"))
      (node (ref "U3") (pin "22") (pinfunction "GND_22") (pintype "power_in"))
      (node (ref "U3") (pin "25") (pinfunction "25_25") (pintype "passive"))
      (node (ref "U4") (pin "111") (pinfunction "VSS(IO)5_111") (pintype "bidirectional"))
      (node (ref "U4") (pin "124") (pinfunction "VSS(IO)6_124") (pintype "bidirectional"))
      (node (ref "U4") (pin "139") (pinfunction "VSS(IO)7_139") (pintype "bidirectional"))
      (node (ref "U4") (pin "150") (pinfunction "VSS(IO)8_150") (pintype "bidirectional"))
      (node (ref "U4") (pin "153") (pinfunction "VREFL_153") (pintype "bidirectional"))
      (node (ref "U4") (pin "156") (pinfunction "AVSS0_156") (pintype "bidirectional"))
      (node (ref "U4") (pin "157") (pinfunction "VREFL0_157") (pintype "bidirectional"))
      (node (ref "U4") (pin "170") (pinfunction "VSS(IO)9_170") (pintype "bidirectional"))
      (node (ref "U4") (pin "22") (pinfunction "VSS1_22") (pintype "bidirectional"))
      (node (ref "U4") (pin "28") (pinfunction "AVSS_USBHS_28") (pintype "bidirectional"))
      (node (ref "U4") (pin "29") (pinfunction "PVSS_USBHS_29") (pintype "bidirectional"))
      (node (ref "U4") (pin "30") (pinfunction "VSS2_USBHS_30") (pintype "bidirectional"))
      (node (ref "U4") (pin "33") (pinfunction "VSS1_USBHS_33") (pintype "bidirectional"))
      (node (ref "U4") (pin "35") (pinfunction "VSSIO_35") (pintype "bidirectional"))
      (node (ref "U4") (pin "45") (pinfunction "VSS_USB_45") (pintype "bidirectional"))
      (node (ref "U4") (pin "60") (pinfunction "VSS(IO)2_60") (pintype "bidirectional"))
      (node (ref "U4") (pin "63") (pinfunction "VSS(IO/DCDC)_63") (pintype "bidirectional"))
      (node (ref "U4") (pin "66") (pinfunction "VCC_DCDC(IO/DCDC)_66") (pintype "bidirectional"))
      (node (ref "U4") (pin "83") (pinfunction "VSS(IO)3_83") (pintype "bidirectional"))
      (node (ref "U4") (pin "98") (pinfunction "VSS(IO)4_98") (pintype "bidirectional"))
      (node (ref "U5") (pin "2") (pinfunction "2_2") (pintype "bidirectional"))
      (node (ref "U5") (pin "4") (pinfunction "4_4") (pintype "bidirectional"))
      (node (ref "X4") (pin "2") (pinfunction "2_2") (pintype "bidirectional"))
      (node (ref "X4") (pin "4") (pinfunction "4_4") (pintype "bidirectional"))
    )
    (net (code "17") (name "GNDE") (class "Default")
      (node (ref "J1") (pin "P$4") (pinfunction "P$4_P$4") (pintype "bidirectional"))
      (node (ref "J2") (pin "P$6") (pinfunction "SHIELD1_P$6") (pintype "bidirectional"))
      (node (ref "J2") (pin "P$7") (pinfunction "SHIELD2_P$7") (pintype "bidirectional"))
      (node (ref "J2") (pin "P$8") (pinfunction "SHIELD3_P$8") (pintype "bidirectional"))
      (node (ref "J2") (pin "P$9") (pinfunction "SHIELD4_P$9") (pintype "bidirectional"))
      (node (ref "J3") (pin "SHLD1") (pinfunction "SHIELD_1_SHLD1") (pintype "bidirectional"))
      (node (ref "J3") (pin "SHLD2") (pinfunction "SHIELD_2_SHLD2") (pintype "bidirectional"))
      (node (ref "J4") (pin "13") (pinfunction "GNDE0_13") (pintype "bidirectional"))
      (node (ref "J4") (pin "14") (pinfunction "GNDE1_14") (pintype "bidirectional"))
      (node (ref "J9") (pin "S1") (pinfunction "SHIELD_S1") (pintype "passive"))
      (node (ref "J9") (pin "S2") (pinfunction "SHIELD_S2") (pintype "passive"))
      (node (ref "J9") (pin "S3") (pinfunction "SHIELD_S3") (pintype "passive"))
      (node (ref "J9") (pin "S4") (pinfunction "SHIELD_S4") (pintype "passive"))
    )
    (net (code "18") (name "ID") (class "Default")
      (node (ref "J2") (pin "P$4") (pinfunction "ID_P$4") (pintype "bidirectional"))
    )
    (net (code "19") (name "IIC_1_SCL") (class "Default")
      (node (ref "J10") (pin "P$5") (pinfunction "P$5_P$5") (pintype "bidirectional"))
      (node (ref "R20") (pin "P$2") (pinfunction "2_P$2") (pintype "passive"))
      (node (ref "U4") (pin "132") (pinfunction "P1_0_132") (pintype "bidirectional"))
    )
    (net (code "20") (name "IIC_1_SDA") (class "Default")
      (node (ref "J10") (pin "P$6") (pinfunction "P$6_P$6") (pintype "bidirectional"))
      (node (ref "R21") (pin "P$2") (pinfunction "2_P$2") (pintype "passive"))
      (node (ref "U4") (pin "131") (pinfunction "P1_1_131") (pintype "bidirectional"))
    )
    (net (code "21") (name "INT_MI_01") (class "Default")
      (node (ref "J10") (pin "P$39") (pinfunction "P$39_P$39") (pintype "bidirectional"))
      (node (ref "U4") (pin "87") (pinfunction "P3_1_87") (pintype "bidirectional"))
    )
    (net (code "22") (name "INT_MI_02") (class "Default")
      (node (ref "J10") (pin "P$40") (pinfunction "P$40_P$40") (pintype "bidirectional"))
      (node (ref "U4") (pin "86") (pinfunction "P3_2_86") (pintype "bidirectional"))
    )
    (net (code "23") (name "INT_MI_03") (class "Default")
      (node (ref "J10") (pin "P$9") (pinfunction "P$9_P$9") (pintype "bidirectional"))
      (node (ref "U4") (pin "128") (pinfunction "P1_4_128") (pintype "bidirectional"))
    )
    (net (code "24") (name "INT_MI_04") (class "Default")
      (node (ref "J10") (pin "P$10") (pinfunction "P$10_P$10") (pintype "bidirectional"))
      (node (ref "U4") (pin "127") (pinfunction "P1_5_127") (pintype "bidirectional"))
    )
    (net (code "25") (name "LED1{slash}SPEED") (class "Default")
      (node (ref "J4") (pin "11") (pinfunction "YLO_11") (pintype "bidirectional"))
      (node (ref "U3") (pin "23") (pinfunction "LED0/ANEN_SPEED_23") (pintype "bidirectional"))
    )
    (net (code "26") (name "NC") (class "Default")
      (node (ref "J4") (pin "7") (pinfunction "P7_7") (pintype "bidirectional"))
    )
    (net (code "27") (name "Net-(C16-1)") (class "Default")
      (node (ref "C16") (pin "P$1") (pinfunction "1_P$1") (pintype "passive"))
      (node (ref "J2") (pin "P$1") (pinfunction "VBUS_P$1") (pintype "bidirectional"))
      (node (ref "R4") (pin "P$2") (pinfunction "2_P$2") (pintype "passive"))
      (node (ref "R7") (pin "P$2") (pinfunction "2_P$2") (pintype "passive"))
    )
    (net (code "28") (name "Net-(C31-1)") (class "Default")
      (node (ref "C31") (pin "P$1") (pinfunction "1_P$1") (pintype "passive"))
      (node (ref "U4") (pin "62") (pinfunction "VCL1_62") (pintype "bidirectional"))
    )
    (net (code "29") (name "Net-(C37-2)") (class "Default")
      (node (ref "C37") (pin "P$2") (pinfunction "2_P$2") (pintype "passive"))
      (node (ref "U4") (pin "148") (pinfunction "VCL2_148") (pintype "bidirectional"))
    )
    (net (code "30") (name "Net-(C38-1)") (class "Default")
      (node (ref "C38") (pin "P$1") (pinfunction "1_P$1") (pintype "passive"))
      (node (ref "U4") (pin "19") (pinfunction "VCLO_19") (pintype "bidirectional"))
    )
    (net (code "31") (name "Net-(C43-1)") (class "Default")
      (node (ref "C43") (pin "P$1") (pinfunction "1_P$1") (pintype "passive"))
      (node (ref "C44") (pin "P$1") (pinfunction "1_P$1") (pintype "passive"))
      (node (ref "FB2/2") (pin "2") (pinfunction "P$2_2") (pintype "bidirectional"))
      (node (ref "U3") (pin "2") (pinfunction "VDDA_3.3_2") (pintype "power_in"))
    )
    (net (code "32") (name "Net-(J2-D+)") (class "Default")
      (node (ref "J2") (pin "P$3") (pinfunction "D+_P$3") (pintype "bidirectional"))
      (node (ref "R6") (pin "P$2") (pinfunction "2_P$2") (pintype "passive"))
    )
    (net (code "33") (name "Net-(J2-D-)") (class "Default")
      (node (ref "J2") (pin "P$2") (pinfunction "D-_P$2") (pintype "bidirectional"))
      (node (ref "R5") (pin "P$2") (pinfunction "2_P$2") (pintype "passive"))
    )
    (net (code "34") (name "Net-(LED3-A)") (class "Default")
      (node (ref "LED3") (pin "1") (pinfunction "A_1") (pintype "passive"))
      (node (ref "R13") (pin "P$1") (pinfunction "1_P$1") (pintype "passive"))
    )
    (net (code "35") (name "Net-(R16-2)") (class "Default")
      (node (ref "R16") (pin "P$2") (pinfunction "2_P$2") (pintype "passive"))
      (node (ref "U4") (pin "65") (pinfunction "VLO2(DCDC)_65") (pintype "bidirectional"))
    )
    (net (code "36") (name "Net-(R17-2)") (class "Default")
      (node (ref "R17") (pin "P$2") (pinfunction "2_P$2") (pintype "passive"))
      (node (ref "U4") (pin "64") (pinfunction "VLO1(DCDC)_64") (pintype "bidirectional"))
    )
    (net (code "37") (name "Net-(R19-2)") (class "Default")
      (node (ref "R19") (pin "P$2") (pinfunction "2_P$2") (pintype "passive"))
      (node (ref "U4") (pin "27") (pinfunction "USBHS_RREF_27") (pintype "bidirectional"))
    )
    (net (code "38") (name "P0_00") (class "Default")
      (node (ref "J5") (pin "P$2") (pinfunction "P$2_P$2") (pintype "bidirectional"))
      (node (ref "U4") (pin "169") (pinfunction "P0_0/AN0\\00_169") (pintype "bidirectional"))
    )
    (net (code "39") (name "P0_01") (class "Default")
      (node (ref "J5") (pin "P$1") (pinfunction "P$1_P$1") (pintype "bidirectional"))
      (node (ref "U4") (pin "168") (pinfunction "P0_1/AN001_168") (pintype "bidirectional"))
    )
    (net (code "40") (name "P0_02") (class "Default")
      (node (ref "J12") (pin "1") (pinfunction "1_1") (pintype "passive"))
      (node (ref "U4") (pin "167") (pinfunction "P0_2/AN002_167") (pintype "bidirectional"))
    )
    (net (code "41") (name "P0_03") (class "Default")
      (node (ref "J12") (pin "3") (pinfunction "3_3") (pintype "passive"))
      (node (ref "U4") (pin "166") (pinfunction "P0_3/PGAVSS000_166") (pintype "bidirectional"))
    )
    (net (code "42") (name "P0_04") (class "Default")
      (node (ref "J12") (pin "5") (pinfunction "5_5") (pintype "passive"))
      (node (ref "U4") (pin "165") (pinfunction "P0_4/AN100_165") (pintype "bidirectional"))
    )
    (net (code "43") (name "P0_05") (class "Default")
      (node (ref "J12") (pin "7") (pinfunction "7_7") (pintype "passive"))
      (node (ref "U4") (pin "164") (pinfunction "P0_5/AN101_164") (pintype "bidirectional"))
    )
    (net (code "44") (name "P0_06") (class "Default")
      (node (ref "J12") (pin "9") (pinfunction "9_9") (pintype "passive"))
      (node (ref "U4") (pin "163") (pinfunction "P0_6/AN102_163") (pintype "bidirectional"))
    )
    (net (code "45") (name "P0_07") (class "Default")
      (node (ref "J12") (pin "10") (pinfunction "10_10") (pintype "passive"))
      (node (ref "U4") (pin "162") (pinfunction "P0_7/PGVSS100_162") (pintype "bidirectional"))
    )
    (net (code "46") (name "P0_08") (class "Default")
      (node (ref "J12") (pin "8") (pinfunction "8_8") (pintype "passive"))
      (node (ref "U4") (pin "161") (pinfunction "P0_8/AN003_161") (pintype "bidirectional"))
    )
    (net (code "47") (name "P0_09") (class "Default")
      (node (ref "J12") (pin "6") (pinfunction "6_6") (pintype "passive"))
      (node (ref "U4") (pin "160") (pinfunction "P0_9/AN004_160") (pintype "bidirectional"))
    )
    (net (code "48") (name "P0_14") (class "Default")
      (node (ref "J12") (pin "4") (pinfunction "4_4") (pintype "passive"))
      (node (ref "U4") (pin "152") (pinfunction "P0_14/DA0/AN005/AN105_152") (pintype "bidirectional"))
    )
    (net (code "49") (name "P0_15") (class "Default")
      (node (ref "J12") (pin "2") (pinfunction "2_2") (pintype "passive"))
      (node (ref "U4") (pin "151") (pinfunction "P0_15/DA1/AN006/AN106_151") (pintype "bidirectional"))
    )
    (net (code "50") (name "P1_02") (class "Default")
      (node (ref "J10") (pin "P$7") (pinfunction "P$7_P$7") (pintype "bidirectional"))
      (node (ref "U4") (pin "130") (pinfunction "P1_2_130") (pintype "bidirectional"))
    )
    (net (code "51") (name "P1_03") (class "Default")
      (node (ref "J10") (pin "P$8") (pinfunction "P$8_P$8") (pintype "bidirectional"))
      (node (ref "U4") (pin "129") (pinfunction "P1_3_129") (pintype "bidirectional"))
    )
    (net (code "52") (name "P1_06") (class "Default")
      (node (ref "J10") (pin "P$11") (pinfunction "P$11_P$11") (pintype "bidirectional"))
      (node (ref "U4") (pin "126") (pinfunction "P1_6_126") (pintype "bidirectional"))
    )
    (net (code "53") (name "P1_07") (class "Default")
      (node (ref "J10") (pin "P$12") (pinfunction "P$12_P$12") (pintype "bidirectional"))
      (node (ref "U4") (pin "125") (pinfunction "P1_7_125") (pintype "bidirectional"))
    )
    (net (code "54") (name "P1_11") (class "Default")
      (node (ref "J10") (pin "P$38") (pinfunction "P$38_P$38") (pintype "bidirectional"))
      (node (ref "U4") (pin "92") (pinfunction "P1_11_92") (pintype "bidirectional"))
    )
    (net (code "55") (name "P1_12") (class "Default")
      (node (ref "J10") (pin "P$37") (pinfunction "P$37_P$37") (pintype "bidirectional"))
      (node (ref "U4") (pin "93") (pinfunction "P1_12_93") (pintype "bidirectional"))
    )
    (net (code "56") (name "P1_13") (class "Default")
      (node (ref "J10") (pin "P$36") (pinfunction "P$36_P$36") (pintype "bidirectional"))
      (node (ref "U4") (pin "94") (pinfunction "P1_13_94") (pintype "bidirectional"))
    )
    (net (code "57") (name "P1_14") (class "Default")
      (node (ref "J10") (pin "P$35") (pinfunction "P$35_P$35") (pintype "bidirectional"))
      (node (ref "U4") (pin "95") (pinfunction "P1_14_95") (pintype "bidirectional"))
    )
    (net (code "58") (name "P1_15") (class "Default")
      (node (ref "J10") (pin "P$34") (pinfunction "P$34_P$34") (pintype "bidirectional"))
      (node (ref "U4") (pin "96") (pinfunction "P1_15_96") (pintype "bidirectional"))
    )
    (net (code "59") (name "P2_00") (class "Default")
      (node (ref "J7") (pin "P$13") (pinfunction "P$13_P$13") (pintype "bidirectional"))
      (node (ref "U4") (pin "69") (pinfunction "P2_0(INPUT_ONLY)_69") (pintype "bidirectional"))
    )
    (net (code "60") (name "P2_01") (class "Default")
      (node (ref "J7") (pin "P$14") (pinfunction "P$14_P$14") (pintype "bidirectional"))
      (node (ref "U4") (pin "68") (pinfunction "P2_1/MD_68") (pintype "bidirectional"))
    )
    (net (code "61") (name "P2_02") (class "Default")
      (node (ref "J7") (pin "P$19") (pinfunction "P$19_P$19") (pintype "bidirectional"))
      (node (ref "U4") (pin "54") (pinfunction "P2_2_54") (pintype "bidirectional"))
    )
    (net (code "62") (name "P2_03") (class "Default")
      (node (ref "J6") (pin "1") (pinfunction "1_1") (pintype "passive"))
      (node (ref "U4") (pin "53") (pinfunction "P2_3_53") (pintype "bidirectional"))
    )
    (net (code "63") (name "P2_04") (class "Default")
      (node (ref "J6") (pin "3") (pinfunction "3_3") (pintype "passive"))
      (node (ref "U4") (pin "52") (pinfunction "P2_4_52") (pintype "bidirectional"))
    )
    (net (code "64") (name "P2_05") (class "Default")
      (node (ref "J6") (pin "5") (pinfunction "5_5") (pintype "passive"))
      (node (ref "U4") (pin "51") (pinfunction "P2_5_51") (pintype "bidirectional"))
    )
    (net (code "65") (name "P2_06") (class "Default")
      (node (ref "J6") (pin "7") (pinfunction "7_7") (pintype "passive"))
      (node (ref "U4") (pin "50") (pinfunction "P2_6_50") (pintype "bidirectional"))
    )
    (net (code "66") (name "P2_07") (class "Default")
      (node (ref "J6") (pin "9") (pinfunction "9_9") (pintype "passive"))
      (node (ref "U4") (pin "49") (pinfunction "P2_7_49") (pintype "bidirectional"))
    )
    (net (code "67") (name "P3_03") (class "Default")
      (node (ref "J7") (pin "P$2") (pinfunction "P$2_P$2") (pintype "bidirectional"))
      (node (ref "U4") (pin "85") (pinfunction "P3_3_85") (pintype "bidirectional"))
    )
    (net (code "68") (name "P3_04") (class "Default")
      (node (ref "J7") (pin "P$4") (pinfunction "P$4_P$4") (pintype "bidirectional"))
      (node (ref "U4") (pin "82") (pinfunction "P3_4_82") (pintype "bidirectional"))
    )
    (net (code "69") (name "P3_05") (class "Default")
      (node (ref "J7") (pin "P$6") (pinfunction "P$6_P$6") (pintype "bidirectional"))
      (node (ref "U4") (pin "81") (pinfunction "P3_5_81") (pintype "bidirectional"))
    )
    (net (code "70") (name "P3_06") (class "Default")
      (node (ref "J7") (pin "P$1") (pinfunction "P$1_P$1") (pintype "bidirectional"))
      (node (ref "U4") (pin "80") (pinfunction "P3_6_80") (pintype "bidirectional"))
    )
    (net (code "71") (name "P3_07") (class "Default")
      (node (ref "J7") (pin "P$3") (pinfunction "P$3_P$3") (pintype "bidirectional"))
      (node (ref "U4") (pin "79") (pinfunction "P3_7_79") (pintype "bidirectional"))
    )
    (net (code "72") (name "P3_09") (class "Default")
      (node (ref "J7") (pin "P$5") (pinfunction "P$5_P$5") (pintype "bidirectional"))
      (node (ref "U4") (pin "77") (pinfunction "P3_9_77") (pintype "bidirectional"))
    )
    (net (code "73") (name "P3_10") (class "Default")
      (node (ref "J7") (pin "P$7") (pinfunction "P$7_P$7") (pintype "bidirectional"))
      (node (ref "U4") (pin "76") (pinfunction "P3_10_76") (pintype "bidirectional"))
    )
    (net (code "74") (name "P3_11") (class "Default")
      (node (ref "J7") (pin "P$8") (pinfunction "P$8_P$8") (pintype "bidirectional"))
      (node (ref "U4") (pin "75") (pinfunction "P3_11_75") (pintype "bidirectional"))
    )
    (net (code "75") (name "P3_12") (class "Default")
      (node (ref "J7") (pin "P$9") (pinfunction "P$9_P$9") (pintype "bidirectional"))
      (node (ref "U4") (pin "74") (pinfunction "P3_12_74") (pintype "bidirectional"))
    )
    (net (code "76") (name "P3_13") (class "Default")
      (node (ref "J7") (pin "P$20") (pinfunction "P$20_P$20") (pintype "bidirectional"))
      (node (ref "U4") (pin "55") (pinfunction "P3_13_55") (pintype "bidirectional"))
    )
    (net (code "77") (name "P3_14") (class "Default")
      (node (ref "J7") (pin "P$17") (pinfunction "P$17_P$17") (pintype "bidirectional"))
      (node (ref "U4") (pin "56") (pinfunction "P3_14_56") (pintype "bidirectional"))
    )
    (net (code "78") (name "P3_15") (class "Default")
      (node (ref "J7") (pin "P$18") (pinfunction "P$18_P$18") (pintype "bidirectional"))
      (node (ref "U4") (pin "57") (pinfunction "P3_15_57") (pintype "bidirectional"))
    )
    (net (code "79") (name "P4_00") (class "Default")
      (node (ref "J5") (pin "P$7") (pinfunction "P$7_P$7") (pintype "bidirectional"))
      (node (ref "U4") (pin "1") (pinfunction "P4_0_1") (pintype "bidirectional"))
    )
    (net (code "80") (name "P4_01") (class "Default")
      (node (ref "J5") (pin "P$8") (pinfunction "P$8_P$8") (pintype "bidirectional"))
      (node (ref "U4") (pin "2") (pinfunction "P4_1_2") (pintype "bidirectional"))
    )
    (net (code "81") (name "P4_02") (class "Default")
      (node (ref "J5") (pin "P$9") (pinfunction "P$9_P$9") (pintype "bidirectional"))
      (node (ref "U4") (pin "3") (pinfunction "P4_2_3") (pintype "bidirectional"))
    )
    (net (code "82") (name "P4_08") (class "Default")
      (node (ref "J5") (pin "P$20") (pinfunction "P$20_P$20") (pintype "bidirectional"))
      (node (ref "U4") (pin "43") (pinfunction "P4_8_43") (pintype "bidirectional"))
    )
    (net (code "83") (name "P4_09") (class "Default")
      (node (ref "J5") (pin "P$19") (pinfunction "P$19_P$19") (pintype "bidirectional"))
      (node (ref "U4") (pin "42") (pinfunction "P4_9_42") (pintype "bidirectional"))
    )
    (net (code "84") (name "P4_10") (class "Default")
      (node (ref "J5") (pin "P$18") (pinfunction "P$18_P$18") (pintype "bidirectional"))
      (node (ref "U4") (pin "41") (pinfunction "P4_10_41") (pintype "bidirectional"))
    )
    (net (code "85") (name "P4_11") (class "Default")
      (node (ref "J5") (pin "P$17") (pinfunction "P$17_P$17") (pintype "bidirectional"))
      (node (ref "U4") (pin "40") (pinfunction "P4_11_40") (pintype "bidirectional"))
    )
    (net (code "86") (name "P4_12") (class "Default")
      (node (ref "J5") (pin "P$16") (pinfunction "P$16_P$16") (pintype "bidirectional"))
      (node (ref "U4") (pin "39") (pinfunction "P4_12_39") (pintype "bidirectional"))
    )
    (net (code "87") (name "P4_13") (class "Default")
      (node (ref "J5") (pin "P$15") (pinfunction "P$15_P$15") (pintype "bidirectional"))
      (node (ref "U4") (pin "38") (pinfunction "P4_13_38") (pintype "bidirectional"))
    )
    (net (code "88") (name "P4_14") (class "Default")
      (node (ref "J5") (pin "P$14") (pinfunction "P$14_P$14") (pintype "bidirectional"))
      (node (ref "U4") (pin "37") (pinfunction "P4_14_37") (pintype "bidirectional"))
    )
    (net (code "89") (name "P4_15") (class "Default")
      (node (ref "J5") (pin "P$13") (pinfunction "P$13_P$13") (pintype "bidirectional"))
      (node (ref "U4") (pin "36") (pinfunction "P4_15_36") (pintype "bidirectional"))
    )
    (net (code "90") (name "P5_11") (class "Default")
      (node (ref "J5") (pin "P$6") (pinfunction "P$6_P$6") (pintype "bidirectional"))
      (node (ref "U4") (pin "176") (pinfunction "P5_11_176") (pintype "bidirectional"))
    )
    (net (code "91") (name "P5_12") (class "Default")
      (node (ref "J5") (pin "P$5") (pinfunction "P$5_P$5") (pintype "bidirectional"))
      (node (ref "U4") (pin "175") (pinfunction "P5_12_175") (pintype "bidirectional"))
    )
    (net (code "92") (name "P5_13") (class "Default")
      (node (ref "J5") (pin "P$4") (pinfunction "P$4_P$4") (pintype "bidirectional"))
      (node (ref "U4") (pin "174") (pinfunction "P5_13_174") (pintype "bidirectional"))
    )
    (net (code "93") (name "P6_00") (class "Default")
      (node (ref "J10") (pin "P$13") (pinfunction "P$13_P$13") (pintype "bidirectional"))
      (node (ref "U4") (pin "122") (pinfunction "P6_0_122") (pintype "bidirectional"))
    )
    (net (code "94") (name "P6_01") (class "Default")
      (node (ref "J10") (pin "P$14") (pinfunction "P$14_P$14") (pintype "bidirectional"))
      (node (ref "U4") (pin "121") (pinfunction "P6_1_121") (pintype "bidirectional"))
    )
    (net (code "95") (name "P6_02") (class "Default")
      (node (ref "J10") (pin "P$15") (pinfunction "P$15_P$15") (pintype "bidirectional"))
      (node (ref "U4") (pin "120") (pinfunction "P6_2_120") (pintype "bidirectional"))
    )
    (net (code "96") (name "P6_03") (class "Default")
      (node (ref "J10") (pin "P$16") (pinfunction "P$16_P$16") (pintype "bidirectional"))
      (node (ref "U4") (pin "119") (pinfunction "P6_3_119") (pintype "bidirectional"))
    )
    (net (code "97") (name "P6_04") (class "Default")
      (node (ref "J10") (pin "P$17") (pinfunction "P$17_P$17") (pintype "bidirectional"))
      (node (ref "U4") (pin "118") (pinfunction "P6_4_118") (pintype "bidirectional"))
    )
    (net (code "98") (name "P6_05") (class "Default")
      (node (ref "J10") (pin "P$18") (pinfunction "P$18_P$18") (pintype "bidirectional"))
      (node (ref "U4") (pin "117") (pinfunction "P6_5_117") (pintype "bidirectional"))
    )
    (net (code "99") (name "P6_06") (class "Default")
      (node (ref "J10") (pin "P$19") (pinfunction "P$19_P$19") (pintype "bidirectional"))
      (node (ref "U4") (pin "116") (pinfunction "P6_6_116") (pintype "bidirectional"))
    )
    (net (code "100") (name "P6_07") (class "Default")
      (node (ref "J10") (pin "P$20") (pinfunction "P$20_P$20") (pintype "bidirectional"))
      (node (ref "U4") (pin "115") (pinfunction "P6_7_115") (pintype "bidirectional"))
    )
    (net (code "101") (name "P6_08") (class "Default")
      (node (ref "J10") (pin "P$33") (pinfunction "P$33_P$33") (pintype "bidirectional"))
      (node (ref "U4") (pin "99") (pinfunction "P6_8_99") (pintype "bidirectional"))
    )
    (net (code "102") (name "P6_09") (class "Default")
      (node (ref "J10") (pin "P$32") (pinfunction "P$32_P$32") (pintype "bidirectional"))
      (node (ref "U4") (pin "100") (pinfunction "P6_9_100") (pintype "bidirectional"))
    )
    (net (code "103") (name "P6_10") (class "Default")
      (node (ref "J10") (pin "P$31") (pinfunction "P$31_P$31") (pintype "bidirectional"))
      (node (ref "U4") (pin "101") (pinfunction "P6_10_101") (pintype "bidirectional"))
    )
    (net (code "104") (name "P6_11") (class "Default")
      (node (ref "J10") (pin "P$30") (pinfunction "P$30_P$30") (pintype "bidirectional"))
      (node (ref "U4") (pin "102") (pinfunction "P6_11_102") (pintype "bidirectional"))
    )
    (net (code "105") (name "P6_12") (class "Default")
      (node (ref "J10") (pin "P$29") (pinfunction "P$29_P$29") (pintype "bidirectional"))
      (node (ref "U4") (pin "103") (pinfunction "P6_12_103") (pintype "bidirectional"))
    )
    (net (code "106") (name "P6_13") (class "Default")
      (node (ref "J10") (pin "P$28") (pinfunction "P$28_P$28") (pintype "bidirectional"))
      (node (ref "U4") (pin "104") (pinfunction "P6_13_104") (pintype "bidirectional"))
    )
    (net (code "107") (name "P6_14") (class "Default")
      (node (ref "J10") (pin "P$27") (pinfunction "P$27_P$27") (pintype "bidirectional"))
      (node (ref "U4") (pin "105") (pinfunction "P6_14_105") (pintype "bidirectional"))
    )
    (net (code "108") (name "P6_15") (class "Default")
      (node (ref "J10") (pin "P$26") (pinfunction "P$26_P$26") (pintype "bidirectional"))
      (node (ref "U4") (pin "106") (pinfunction "P6_15_106") (pintype "bidirectional"))
    )
    (net (code "109") (name "P7_06") (class "Default")
      (node (ref "J5") (pin "P$10") (pinfunction "P$10_P$10") (pintype "bidirectional"))
      (node (ref "U4") (pin "14") (pinfunction "P7_6_14") (pintype "bidirectional"))
    )
    (net (code "110") (name "P7_07") (class "Default")
      (node (ref "J5") (pin "P$11") (pinfunction "P$11_P$11") (pintype "bidirectional"))
      (node (ref "U4") (pin "15") (pinfunction "P7_7_15") (pintype "bidirectional"))
    )
    (net (code "111") (name "P8_00") (class "Default")
      (node (ref "J10") (pin "P$4") (pinfunction "P$4_P$4") (pintype "bidirectional"))
      (node (ref "U4") (pin "133") (pinfunction "P8_0_133") (pintype "bidirectional"))
    )
    (net (code "112") (name "P8_01") (class "Default")
      (node (ref "J10") (pin "P$3") (pinfunction "P$3_P$3") (pintype "bidirectional"))
      (node (ref "U4") (pin "134") (pinfunction "P8_1_134") (pintype "bidirectional"))
    )
    (net (code "113") (name "P8_02") (class "Default")
      (node (ref "J10") (pin "P$2") (pinfunction "P$2_P$2") (pintype "bidirectional"))
      (node (ref "U4") (pin "135") (pinfunction "P8_2_135") (pintype "bidirectional"))
    )
    (net (code "114") (name "P8_03") (class "Default")
      (node (ref "U4") (pin "136") (pinfunction "P8_3_136") (pintype "bidirectional"))
    )
    (net (code "115") (name "P8_04") (class "Default")
      (node (ref "U4") (pin "137") (pinfunction "P8_4_137") (pintype "bidirectional"))
    )
    (net (code "116") (name "P8_05") (class "Default")
      (node (ref "J5") (pin "P$3") (pinfunction "P$3_P$3") (pintype "bidirectional"))
      (node (ref "U4") (pin "173") (pinfunction "P8_5_173") (pintype "bidirectional"))
    )
    (net (code "117") (name "P9_00") (class "Default")
      (node (ref "J7") (pin "P$16") (pinfunction "P$16_P$16") (pintype "bidirectional"))
      (node (ref "U4") (pin "58") (pinfunction "P9_0_58") (pintype "bidirectional"))
    )
    (net (code "118") (name "P9_01") (class "Default")
      (node (ref "J7") (pin "P$15") (pinfunction "P$15_P$15") (pintype "bidirectional"))
      (node (ref "U4") (pin "59") (pinfunction "P9_1_59") (pintype "bidirectional"))
    )
    (net (code "119") (name "P9_05") (class "Default")
      (node (ref "J7") (pin "P$10") (pinfunction "P$10_P$10") (pintype "bidirectional"))
      (node (ref "U4") (pin "73") (pinfunction "P9_5_73") (pintype "bidirectional"))
    )
    (net (code "120") (name "P9_06") (class "Default")
      (node (ref "J7") (pin "P$11") (pinfunction "P$11_P$11") (pintype "bidirectional"))
      (node (ref "U4") (pin "72") (pinfunction "P9_6_72") (pintype "bidirectional"))
    )
    (net (code "121") (name "P9_07") (class "Default")
      (node (ref "J7") (pin "P$12") (pinfunction "P$12_P$12") (pintype "bidirectional"))
      (node (ref "U4") (pin "71") (pinfunction "P9_7_71") (pintype "bidirectional"))
    )
    (net (code "122") (name "P9_08") (class "Default")
      (node (ref "U4") (pin "70") (pinfunction "P9_8_70") (pintype "bidirectional"))
    )
    (net (code "123") (name "PA_00") (class "Default")
      (node (ref "J10") (pin "P$21") (pinfunction "P$21_P$21") (pintype "bidirectional"))
      (node (ref "U4") (pin "114") (pinfunction "PA_0_114") (pintype "bidirectional"))
    )
    (net (code "124") (name "PA_01") (class "Default")
      (node (ref "J10") (pin "P$22") (pinfunction "P$22_P$22") (pintype "bidirectional"))
      (node (ref "U4") (pin "113") (pinfunction "PA_1_113") (pintype "bidirectional"))
    )
    (net (code "125") (name "PA_08") (class "Default")
      (node (ref "J10") (pin "P$25") (pinfunction "P$25_P$25") (pintype "bidirectional"))
      (node (ref "U4") (pin "107") (pinfunction "PA_8_107") (pintype "bidirectional"))
    )
    (net (code "126") (name "PA_09") (class "Default")
      (node (ref "J10") (pin "P$24") (pinfunction "P$24_P$24") (pintype "bidirectional"))
      (node (ref "U4") (pin "108") (pinfunction "PA_9_108") (pintype "bidirectional"))
    )
    (net (code "127") (name "PA_10") (class "Default")
      (node (ref "J10") (pin "P$23") (pinfunction "P$23_P$23") (pintype "bidirectional"))
      (node (ref "U4") (pin "109") (pinfunction "PA_10_109") (pintype "bidirectional"))
    )
    (net (code "128") (name "PB_00") (class "Default")
      (node (ref "J5") (pin "P$12") (pinfunction "P$12_P$12") (pintype "bidirectional"))
      (node (ref "U4") (pin "16") (pinfunction "PB_0_16") (pintype "bidirectional"))
    )
    (net (code "129") (name "R51") (class "Default")
      (node (ref "J4") (pin "12") (pinfunction "YHI_12") (pintype "bidirectional"))
      (node (ref "R23") (pin "P$1") (pinfunction "1_P$1") (pintype "passive"))
    )
    (net (code "130") (name "R52") (class "Default")
      (node (ref "J4") (pin "9") (pinfunction "GHI_9") (pintype "bidirectional"))
      (node (ref "R24") (pin "P$1") (pinfunction "1_P$1") (pintype "passive"))
    )
    (net (code "131") (name "RESET") (class "Default")
      (node (ref "C57") (pin "P$1") (pinfunction "1_P$1") (pintype "passive"))
      (node (ref "J11") (pin "9") (pinfunction "9_9") (pintype "passive"))
      (node (ref "R18") (pin "P$1") (pinfunction "1_P$1") (pintype "passive"))
      (node (ref "U4") (pin "67") (pinfunction "RES#_67") (pintype "bidirectional"))
    )
    (net (code "132") (name "REXT") (class "Default")
      (node (ref "C47") (pin "P$1") (pinfunction "1_P$1") (pintype "passive"))
      (node (ref "R25") (pin "P$2") (pinfunction "2_P$2") (pintype "passive"))
      (node (ref "U3") (pin "9") (pinfunction "REXT_9") (pintype "input"))
    )
    (net (code "133") (name "RXD0") (class "Default")
      (node (ref "R31") (pin "P$2") (pinfunction "2_P$2") (pintype "passive"))
      (node (ref "U3") (pin "13") (pinfunction "RXD0_13") (pintype "bidirectional"))
    )
    (net (code "134") (name "RXD1") (class "Default")
      (node (ref "R30") (pin "P$2") (pinfunction "2_P$2") (pintype "passive"))
      (node (ref "U3") (pin "12") (pinfunction "RXD1_12") (pintype "bidirectional"))
    )
    (net (code "135") (name "RXER") (class "Default")
      (node (ref "R32") (pin "P$2") (pinfunction "2_P$2") (pintype "passive"))
      (node (ref "U3") (pin "17") (pinfunction "RXER_17") (pintype "bidirectional"))
    )
    (net (code "136") (name "RXM") (class "Default")
      (node (ref "J4") (pin "6") (pinfunction "RD-_6") (pintype "bidirectional"))
      (node (ref "U3") (pin "3") (pinfunction "RXM_3") (pintype "bidirectional"))
    )
    (net (code "137") (name "RXP") (class "Default")
      (node (ref "J4") (pin "3") (pinfunction "RD+_3") (pintype "bidirectional"))
      (node (ref "U3") (pin "4") (pinfunction "RXP_4") (pintype "bidirectional"))
    )
    (net (code "138") (name "SD1_CD") (class "Default")
      (node (ref "J9") (pin "10") (pinfunction "CD_SWITCH2_10") (pintype "bidirectional"))
      (node (ref "U4") (pin "146") (pinfunction "P5_6/AN019_146") (pintype "bidirectional"))
    )
    (net (code "139") (name "SD1_CLK") (class "Default")
      (node (ref "J9") (pin "5") (pinfunction "CLOCK_5") (pintype "bidirectional"))
      (node (ref "U4") (pin "140") (pinfunction "P5_0/AN016_140") (pintype "bidirectional"))
    )
    (net (code "140") (name "SD1_CMD") (class "Default")
      (node (ref "J9") (pin "3") (pinfunction "COMMAND/RESPONSE_3") (pintype "bidirectional"))
      (node (ref "U4") (pin "141") (pinfunction "P5_1/AN116_141") (pintype "bidirectional"))
    )
    (net (code "141") (name "SD1_DAT0") (class "Default")
      (node (ref "J9") (pin "7") (pinfunction "DATA_LINE[BIT_0]_7") (pintype "bidirectional"))
      (node (ref "U4") (pin "142") (pinfunction "P5_2/AN017_142") (pintype "bidirectional"))
    )
    (net (code "142") (name "SD1_DAT1") (class "Default")
      (node (ref "J9") (pin "8") (pinfunction "DATA_LINE[BIT_1]_8") (pintype "bidirectional"))
      (node (ref "U4") (pin "143") (pinfunction "P5_3/AN117_143") (pintype "bidirectional"))
    )
    (net (code "143") (name "SD1_DAT2") (class "Default")
      (node (ref "J9") (pin "1") (pinfunction "DATA_LINE[BIT_2]_1") (pintype "bidirectional"))
      (node (ref "U4") (pin "144") (pinfunction "P5_4/AN018_144") (pintype "bidirectional"))
    )
    (net (code "144") (name "SD1_DAT3") (class "Default")
      (node (ref "J9") (pin "2") (pinfunction "CARD_DETECT/DATA_LINE[BIT_3]_2") (pintype "bidirectional"))
      (node (ref "U4") (pin "145") (pinfunction "P5_5/AN118_145") (pintype "bidirectional"))
    )
    (net (code "145") (name "SD1_WP") (class "Default")
      (node (ref "J9") (pin "9") (pinfunction "CD_SWITCH1_9") (pintype "bidirectional"))
      (node (ref "U4") (pin "147") (pinfunction "P5_7/AN119_147") (pintype "bidirectional"))
    )
    (net (code "146") (name "TCK") (class "Default")
      (node (ref "J11") (pin "7") (pinfunction "7_7") (pintype "passive"))
      (node (ref "U4") (pin "88") (pinfunction "P3_0_88") (pintype "bidirectional"))
    )
    (net (code "147") (name "TDI") (class "Default")
      (node (ref "J11") (pin "1") (pinfunction "1_1") (pintype "passive"))
      (node (ref "U4") (pin "91") (pinfunction "P1_10_91") (pintype "bidirectional"))
    )
    (net (code "148") (name "TDO") (class "Default")
      (node (ref "J11") (pin "3") (pinfunction "3_3") (pintype "passive"))
      (node (ref "U4") (pin "90") (pinfunction "P1_9_90") (pintype "bidirectional"))
    )
    (net (code "149") (name "TMS") (class "Default")
      (node (ref "J11") (pin "5") (pinfunction "5_5") (pintype "passive"))
      (node (ref "U4") (pin "89") (pinfunction "P1_8_89") (pintype "bidirectional"))
    )
    (net (code "150") (name "TXM") (class "Default")
      (node (ref "J4") (pin "2") (pinfunction "TD-_2") (pintype "bidirectional"))
      (node (ref "U3") (pin "5") (pinfunction "TXM_5") (pintype "bidirectional"))
    )
    (net (code "151") (name "TXP") (class "Default")
      (node (ref "J4") (pin "1") (pinfunction "TD+_1") (pintype "bidirectional"))
      (node (ref "U3") (pin "6") (pinfunction "TXP_6") (pintype "bidirectional"))
    )
    (net (code "152") (name "USBHS_FAULT") (class "Default")
      (node (ref "R12") (pin "P$1") (pinfunction "1_P$1") (pintype "passive"))
      (node (ref "U2") (pin "3") (pinfunction "FLG_3") (pintype "input"))
      (node (ref "U4") (pin "78") (pinfunction "P3_8_78") (pintype "bidirectional"))
    )
    (net (code "153") (name "USBHS_N") (class "Default")
      (node (ref "J3") (pin "D-") (pinfunction "D-_D-") (pintype "bidirectional"))
      (node (ref "U4") (pin "31") (pinfunction "USBHS_DM_31") (pintype "bidirectional"))
    )
    (net (code "154") (name "USBHS_P") (class "Default")
      (node (ref "J3") (pin "D+") (pinfunction "D+_D+") (pintype "bidirectional"))
      (node (ref "U4") (pin "32") (pinfunction "USBHS_DP_32") (pintype "bidirectional"))
    )
    (net (code "155") (name "USBHS_VBUS") (class "Default")
      (node (ref "C11") (pin "P$1") (pinfunction "1_P$1") (pintype "passive"))
      (node (ref "C15") (pin "1") (pinfunction "1_1") (pintype "passive"))
      (node (ref "J3") (pin "VBUS") (pinfunction "VBUS_VBUS") (pintype "power_in"))
      (node (ref "U2") (pin "5") (pinfunction "OUT_5") (pintype "input"))
      (node (ref "U4") (pin "17") (pinfunction "PB_1_17") (pintype "bidirectional"))
    )
    (net (code "156") (name "USBHS_VBUSEN") (class "Default")
      (node (ref "R1") (pin "P$1") (pinfunction "1_P$1") (pintype "passive"))
      (node (ref "U2") (pin "1") (pinfunction "EN_1") (pintype "input"))
    )
    (net (code "157") (name "USB_N") (class "Default")
      (node (ref "R5") (pin "P$1") (pinfunction "1_P$1") (pintype "passive"))
      (node (ref "U4") (pin "46") (pinfunction "USB_DM_46") (pintype "bidirectional"))
    )
    (net (code "158") (name "USB_P") (class "Default")
      (node (ref "R6") (pin "P$1") (pinfunction "1_P$1") (pintype "passive"))
      (node (ref "U4") (pin "47") (pinfunction "USB_DP_47") (pintype "bidirectional"))
    )
    (net (code "159") (name "USB_VBUS_B") (class "Default")
      (node (ref "R4") (pin "P$1") (pinfunction "1_P$1") (pintype "passive"))
      (node (ref "U4") (pin "44") (pinfunction "P4_7_44") (pintype "bidirectional"))
    )
    (net (code "160") (name "VCL_F(FLASH)") (class "Default")
      (node (ref "C36") (pin "P$2") (pinfunction "2_P$2") (pintype "passive"))
      (node (ref "U4") (pin "112") (pinfunction "VCL_F(FLASH)_112") (pintype "bidirectional"))
    )
    (net (code "161") (name "VDD") (class "Default")
      (node (ref "C1") (pin "P$2") (pinfunction "2_P$2") (pintype "passive"))
      (node (ref "C10") (pin "P$2") (pinfunction "2_P$2") (pintype "passive"))
      (node (ref "C13") (pin "P$2") (pinfunction "2_P$2") (pintype "passive"))
      (node (ref "C14") (pin "P$2") (pinfunction "2_P$2") (pintype "passive"))
      (node (ref "C2") (pin "P$2") (pinfunction "2_P$2") (pintype "passive"))
      (node (ref "C30") (pin "P$2") (pinfunction "2_P$2") (pintype "passive"))
      (node (ref "C32") (pin "P$1") (pinfunction "1_P$1") (pintype "passive"))
      (node (ref "C33") (pin "P$1") (pinfunction "1_P$1") (pintype "passive"))
      (node (ref "C34") (pin "P$1") (pinfunction "1_P$1") (pintype "passive"))
      (node (ref "C35") (pin "P$1") (pinfunction "1_P$1") (pintype "passive"))
      (node (ref "C48") (pin "P$1") (pinfunction "1_P$1") (pintype "passive"))
      (node (ref "C49") (pin "P$1") (pinfunction "1_P$1") (pintype "passive"))
      (node (ref "C54") (pin "P$2") (pinfunction "2_P$2") (pintype "passive"))
      (node (ref "C55") (pin "P$2") (pinfunction "2_P$2") (pintype "passive"))
      (node (ref "C56") (pin "P$2") (pinfunction "2_P$2") (pintype "passive"))
      (node (ref "C58") (pin "P$1") (pinfunction "1_P$1") (pintype "passive"))
      (node (ref "C59") (pin "P$1") (pinfunction "1_P$1") (pintype "passive"))
      (node (ref "C60") (pin "P$1") (pinfunction "1_P$1") (pintype "passive"))
      (node (ref "C61") (pin "P$2") (pinfunction "2_P$2") (pintype "passive"))
      (node (ref "FB2/2") (pin "1") (pinfunction "P$1_1") (pintype "bidirectional"))
      (node (ref "J11") (pin "2") (pinfunction "2_2") (pintype "passive"))
      (node (ref "J11") (pin "4") (pinfunction "4_4") (pintype "passive"))
      (node (ref "J9") (pin "4") (pinfunction "SUPPLY_VOLTAGE_4") (pintype "power_in"))
      (node (ref "L3") (pin "2") (pinfunction "P$2_2") (pintype "bidirectional"))
      (node (ref "R13") (pin "P$2") (pinfunction "2_P$2") (pintype "passive"))
      (node (ref "R18") (pin "P$2") (pinfunction "2_P$2") (pintype "passive"))
      (node (ref "R20") (pin "P$1") (pinfunction "1_P$1") (pintype "passive"))
      (node (ref "R21") (pin "P$1") (pinfunction "1_P$1") (pintype "passive"))
      (node (ref "R23") (pin "P$2") (pinfunction "2_P$2") (pintype "passive"))
      (node (ref "R24") (pin "P$2") (pinfunction "2_P$2") (pintype "passive"))
      (node (ref "R26") (pin "P$2") (pinfunction "2_P$2") (pintype "passive"))
      (node (ref "R27") (pin "P$2") (pinfunction "2_P$2") (pintype "passive"))
      (node (ref "R28") (pin "P$2") (pinfunction "2_P$2") (pintype "passive"))
      (node (ref "R29") (pin "P$2") (pinfunction "2_P$2") (pintype "passive"))
      (node (ref "U3") (pin "14") (pinfunction "VDDIO_14") (pintype "power_in"))
      (node (ref "U4") (pin "110") (pinfunction "VCC(IO)5_110") (pintype "bidirectional"))
      (node (ref "U4") (pin "123") (pinfunction "VCC(IO)6_123") (pintype "bidirectional"))
      (node (ref "U4") (pin "138") (pinfunction "VCC(IO)7_138") (pintype "bidirectional"))
      (node (ref "U4") (pin "149") (pinfunction "VCC(IO)8_149") (pintype "bidirectional"))
      (node (ref "U4") (pin "154") (pinfunction "VREFH_154") (pintype "bidirectional"))
      (node (ref "U4") (pin "155") (pinfunction "AVCC0_155") (pintype "bidirectional"))
      (node (ref "U4") (pin "158") (pinfunction "VREFH0_158") (pintype "bidirectional"))
      (node (ref "U4") (pin "171") (pinfunction "VCC(IO)9_171") (pintype "bidirectional"))
      (node (ref "U4") (pin "25") (pinfunction "VCC1_25") (pintype "bidirectional"))
      (node (ref "U4") (pin "26") (pinfunction "AVCC_SUBHS_26") (pintype "bidirectional"))
      (node (ref "U4") (pin "34") (pinfunction "VCC_USBHS_34") (pintype "bidirectional"))
      (node (ref "U4") (pin "48") (pinfunction "VCC_USB_48") (pintype "bidirectional"))
      (node (ref "U4") (pin "61") (pinfunction "VCC(IO)2_61") (pintype "bidirectional"))
      (node (ref "U4") (pin "84") (pinfunction "VCC(IO)3_84") (pintype "bidirectional"))
      (node (ref "U4") (pin "97") (pinfunction "VCC(IO)4_97") (pintype "bidirectional"))
    )
    (net (code "162") (name "VDD5") (class "Default")
      (node (ref "C5") (pin "P$1") (pinfunction "1_P$1") (pintype "passive"))
      (node (ref "C8") (pin "P$1") (pinfunction "1_P$1") (pintype "passive"))
      (node (ref "J1") (pin "P$3") (pinfunction "P$3_P$3") (pintype "bidirectional"))
      (node (ref "R1") (pin "P$2") (pinfunction "2_P$2") (pintype "passive"))
      (node (ref "R12") (pin "P$2") (pinfunction "2_P$2") (pintype "passive"))
      (node (ref "U2") (pin "4") (pinfunction "VIN_4") (pintype "input"))
    )
    (net (code "163") (name "VDDIN") (class "Default")
      (node (ref "J1") (pin "P$2") (pinfunction "P$2_P$2") (pintype "bidirectional"))
      (node (ref "L3") (pin "1") (pinfunction "P$1_1") (pintype "bidirectional"))
    )
    (net (code "164") (name "VDD_1.2") (class "Default")
      (node (ref "C45") (pin "P$1") (pinfunction "1_P$1") (pintype "passive"))
      (node (ref "C46") (pin "P$1") (pinfunction "1_P$1") (pintype "passive"))
      (node (ref "U3") (pin "1") (pinfunction "VDD_1.2_1") (pintype "power_in"))
    )
    (net (code "165") (name "XCIN") (class "Default")
      (node (ref "C50") (pin "P$1") (pinfunction "1_P$1") (pintype "passive"))
      (node (ref "U4") (pin "20") (pinfunction "XCIN_20") (pintype "bidirectional"))
      (node (ref "X3") (pin "P$1") (pinfunction "P$1_P$1") (pintype "bidirectional"))
    )
    (net (code "166") (name "XCOUT") (class "Default")
      (node (ref "C51") (pin "P$1") (pinfunction "1_P$1") (pintype "passive"))
      (node (ref "U4") (pin "21") (pinfunction "XCOUT_21") (pintype "bidirectional"))
      (node (ref "X3") (pin "P$2") (pinfunction "P$2_P$2") (pintype "bidirectional"))
    )
    (net (code "167") (name "XII") (class "Default")
      (node (ref "C42") (pin "P$1") (pinfunction "1_P$1") (pintype "passive"))
      (node (ref "U3") (pin "8") (pinfunction "XI_8") (pintype "input"))
      (node (ref "U5") (pin "1") (pinfunction "1_1") (pintype "bidirectional"))
    )
    (net (code "168") (name "XOO") (class "Default")
      (node (ref "C41") (pin "P$1") (pinfunction "1_P$1") (pintype "passive"))
      (node (ref "U3") (pin "7") (pinfunction "XO_7") (pintype "output"))
      (node (ref "U5") (pin "3") (pinfunction "3_3") (pintype "bidirectional"))
    )
    (net (code "169") (name "XTAL1") (class "Default")
      (node (ref "C52") (pin "P$1") (pinfunction "1_P$1") (pintype "passive"))
      (node (ref "U4") (pin "23") (pinfunction "P2_13/XTAL_23") (pintype "bidirectional"))
      (node (ref "X4") (pin "1") (pinfunction "1_1") (pintype "bidirectional"))
    )
    (net (code "170") (name "XTAL2") (class "Default")
      (node (ref "C53") (pin "P$1") (pinfunction "1_P$1") (pintype "passive"))
      (node (ref "U4") (pin "24") (pinfunction "P2_12/EXTAL_24") (pintype "bidirectional"))
      (node (ref "X4") (pin "3") (pinfunction "3_3") (pintype "bidirectional"))
    )
    (net (code "171") (name "unconnected-(U4-VBAT-Pad18)") (class "Default")
      (node (ref "U4") (pin "18") (pinfunction "VBAT_18") (pintype "bidirectional"))
    )
  )
)
